# Light_Table_Board.net
KiCad netlist of a schematic drawn in EAGLE
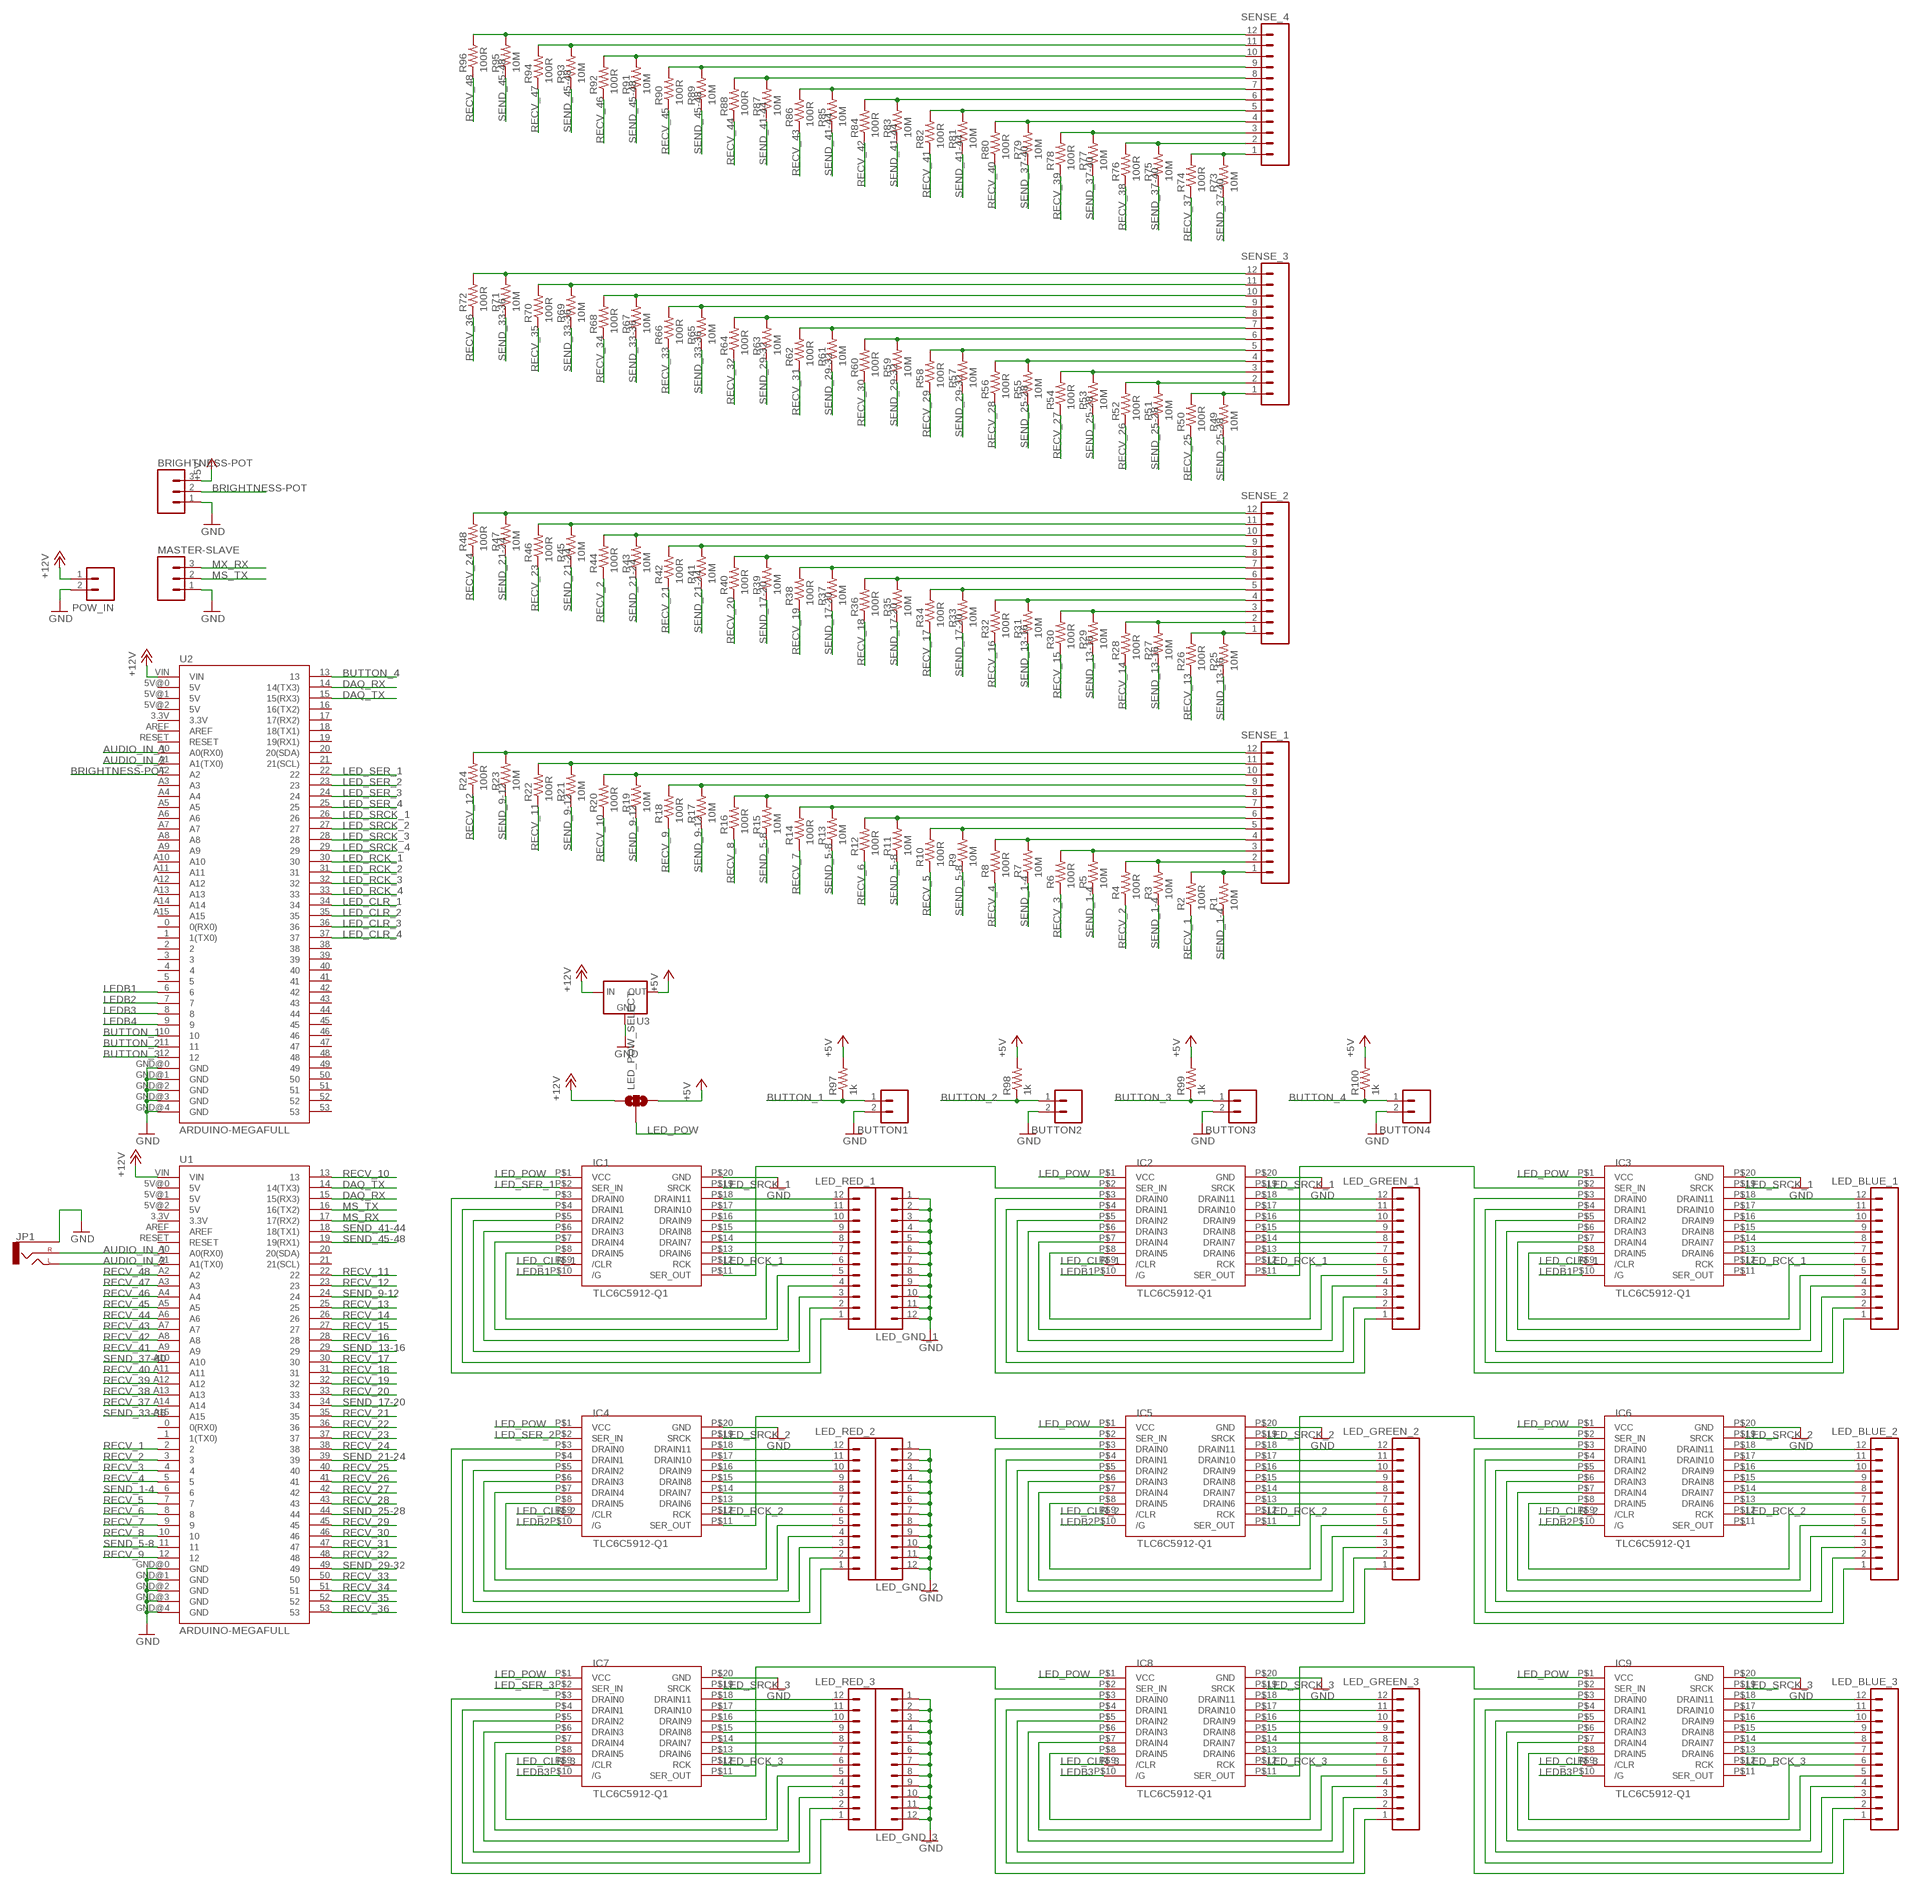
[diagram p0: schematic, sheet 1, part 1 of 2]
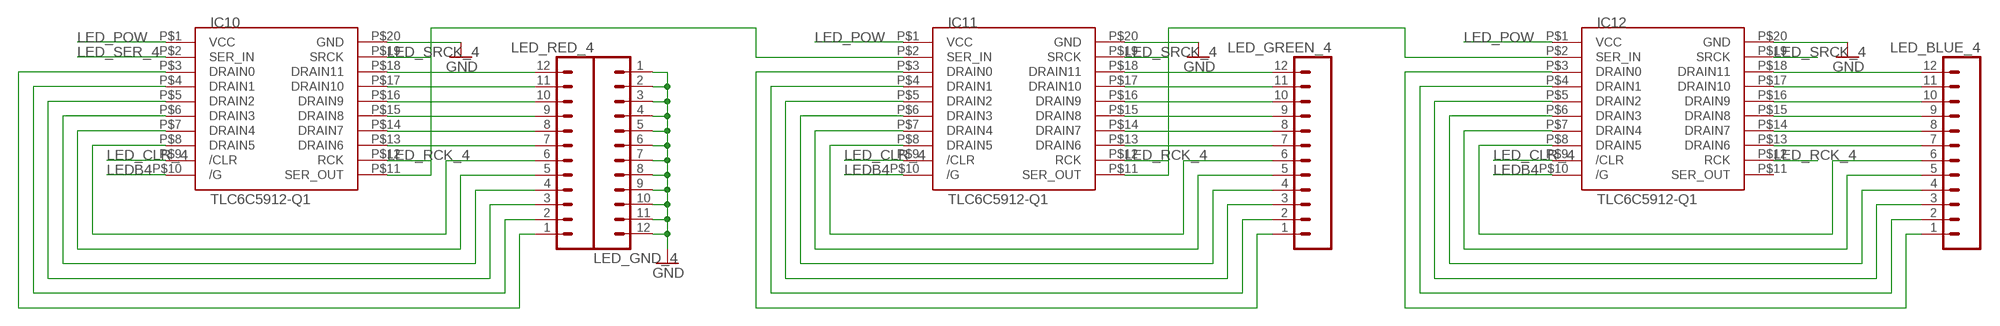
[diagram p1: schematic, sheet 1, part 2 of 2]

(export (version "E")
  (design (tool "Eeschema 10.0.6"))
  (components
    (comp (ref "BRIGHTNESS-POT")
      (value "M03SCREW")
      (footprint "eagle-import:SCREWTERMINAL-3.5MM-3")
      (libsource (lib "eagle-import") (part "M03SCREW"))
    )
    (comp (ref "BUTTON1")
      (value "M023.5MM-NO_SILK")
      (footprint "eagle-import:SCREWTERMINAL-3.5MM-2-NS")
      (libsource (lib "eagle-import") (part "M023.5MM-NO_SILK"))
    )
    (comp (ref "BUTTON2")
      (value "M023.5MM-NO_SILK")
      (footprint "eagle-import:SCREWTERMINAL-3.5MM-2-NS")
      (libsource (lib "eagle-import") (part "M023.5MM-NO_SILK"))
    )
    (comp (ref "BUTTON3")
      (value "M023.5MM-NO_SILK")
      (footprint "eagle-import:SCREWTERMINAL-3.5MM-2-NS")
      (libsource (lib "eagle-import") (part "M023.5MM-NO_SILK"))
    )
    (comp (ref "BUTTON4")
      (value "M023.5MM-NO_SILK")
      (footprint "eagle-import:SCREWTERMINAL-3.5MM-2-NS")
      (libsource (lib "eagle-import") (part "M023.5MM-NO_SILK"))
    )
    (comp (ref "IC1")
      (value "TLC6C5912-Q1")
      (footprint "eagle-import:SOIC-20")
      (libsource (lib "eagle-import") (part "TLC6C5912-Q1"))
    )
    (comp (ref "IC2")
      (value "TLC6C5912-Q1")
      (footprint "eagle-import:SOIC-20")
      (libsource (lib "eagle-import") (part "TLC6C5912-Q1"))
    )
    (comp (ref "IC3")
      (value "TLC6C5912-Q1")
      (footprint "eagle-import:SOIC-20")
      (libsource (lib "eagle-import") (part "TLC6C5912-Q1"))
    )
    (comp (ref "IC4")
      (value "TLC6C5912-Q1")
      (footprint "eagle-import:SOIC-20")
      (libsource (lib "eagle-import") (part "TLC6C5912-Q1"))
    )
    (comp (ref "IC5")
      (value "TLC6C5912-Q1")
      (footprint "eagle-import:SOIC-20")
      (libsource (lib "eagle-import") (part "TLC6C5912-Q1"))
    )
    (comp (ref "IC6")
      (value "TLC6C5912-Q1")
      (footprint "eagle-import:SOIC-20")
      (libsource (lib "eagle-import") (part "TLC6C5912-Q1"))
    )
    (comp (ref "IC7")
      (value "TLC6C5912-Q1")
      (footprint "eagle-import:SOIC-20")
      (libsource (lib "eagle-import") (part "TLC6C5912-Q1"))
    )
    (comp (ref "IC8")
      (value "TLC6C5912-Q1")
      (footprint "eagle-import:SOIC-20")
      (libsource (lib "eagle-import") (part "TLC6C5912-Q1"))
    )
    (comp (ref "IC9")
      (value "TLC6C5912-Q1")
      (footprint "eagle-import:SOIC-20")
      (libsource (lib "eagle-import") (part "TLC6C5912-Q1"))
    )
    (comp (ref "IC10")
      (value "TLC6C5912-Q1")
      (footprint "eagle-import:SOIC-20")
      (libsource (lib "eagle-import") (part "TLC6C5912-Q1"))
    )
    (comp (ref "IC11")
      (value "TLC6C5912-Q1")
      (footprint "eagle-import:SOIC-20")
      (libsource (lib "eagle-import") (part "TLC6C5912-Q1"))
    )
    (comp (ref "IC12")
      (value "TLC6C5912-Q1")
      (footprint "eagle-import:SOIC-20")
      (libsource (lib "eagle-import") (part "TLC6C5912-Q1"))
    )
    (comp (ref "JP1")
      (value "AUDIO-JACK2.5MM")
      (footprint "eagle-import:STEREOJACK2.5MM_STEREOJACK2.5MM")
      (libsource (lib "eagle-import") (part "AUDIO-JACK2.5MM"))
    )
    (comp (ref "LED_BLUE_1")
      (value "M12LONGPADS")
      (footprint "eagle-import:1X12_LONGPADS")
      (libsource (lib "eagle-import") (part "M12LONGPADS"))
    )
    (comp (ref "LED_BLUE_2")
      (value "M12LONGPADS")
      (footprint "eagle-import:1X12_LONGPADS")
      (libsource (lib "eagle-import") (part "M12LONGPADS"))
    )
    (comp (ref "LED_BLUE_3")
      (value "M12LONGPADS")
      (footprint "eagle-import:1X12_LONGPADS")
      (libsource (lib "eagle-import") (part "M12LONGPADS"))
    )
    (comp (ref "LED_BLUE_4")
      (value "M12LONGPADS")
      (footprint "eagle-import:1X12_LONGPADS")
      (libsource (lib "eagle-import") (part "M12LONGPADS"))
    )
    (comp (ref "LED_GND_1")
      (value "M12LONGPADS")
      (footprint "eagle-import:1X12_LONGPADS")
      (libsource (lib "eagle-import") (part "M12LONGPADS"))
    )
    (comp (ref "LED_GND_2")
      (value "M12LONGPADS")
      (footprint "eagle-import:1X12_LONGPADS")
      (libsource (lib "eagle-import") (part "M12LONGPADS"))
    )
    (comp (ref "LED_GND_3")
      (value "M12LONGPADS")
      (footprint "eagle-import:1X12_LONGPADS")
      (libsource (lib "eagle-import") (part "M12LONGPADS"))
    )
    (comp (ref "LED_GND_4")
      (value "M12LONGPADS")
      (footprint "eagle-import:1X12_LONGPADS")
      (libsource (lib "eagle-import") (part "M12LONGPADS"))
    )
    (comp (ref "LED_GREEN_1")
      (value "M12LONGPADS")
      (footprint "eagle-import:1X12_LONGPADS")
      (libsource (lib "eagle-import") (part "M12LONGPADS"))
    )
    (comp (ref "LED_GREEN_2")
      (value "M12LONGPADS")
      (footprint "eagle-import:1X12_LONGPADS")
      (libsource (lib "eagle-import") (part "M12LONGPADS"))
    )
    (comp (ref "LED_GREEN_3")
      (value "M12LONGPADS")
      (footprint "eagle-import:1X12_LONGPADS")
      (libsource (lib "eagle-import") (part "M12LONGPADS"))
    )
    (comp (ref "LED_GREEN_4")
      (value "M12LONGPADS")
      (footprint "eagle-import:1X12_LONGPADS")
      (libsource (lib "eagle-import") (part "M12LONGPADS"))
    )
    (comp (ref "LED_POW_SELECT")
      (value "SOLDERJUMPER_2WAYS")
      (footprint "eagle-import:SJ_3")
      (libsource (lib "eagle-import") (part "SOLDERJUMPER_2WAYS"))
    )
    (comp (ref "LED_RED_1")
      (value "M12LONGPADS")
      (footprint "eagle-import:1X12_LONGPADS")
      (libsource (lib "eagle-import") (part "M12LONGPADS"))
    )
    (comp (ref "LED_RED_2")
      (value "M12LONGPADS")
      (footprint "eagle-import:1X12_LONGPADS")
      (libsource (lib "eagle-import") (part "M12LONGPADS"))
    )
    (comp (ref "LED_RED_3")
      (value "M12LONGPADS")
      (footprint "eagle-import:1X12_LONGPADS")
      (libsource (lib "eagle-import") (part "M12LONGPADS"))
    )
    (comp (ref "LED_RED_4")
      (value "M12LONGPADS")
      (footprint "eagle-import:1X12_LONGPADS")
      (libsource (lib "eagle-import") (part "M12LONGPADS"))
    )
    (comp (ref "MASTER-SLAVE")
      (value "M03SCREW")
      (footprint "eagle-import:SCREWTERMINAL-3.5MM-3")
      (libsource (lib "eagle-import") (part "M03SCREW"))
    )
    (comp (ref "POW_IN")
      (value "M023.5MM-NO_SILK")
      (footprint "eagle-import:SCREWTERMINAL-3.5MM-2-NS")
      (libsource (lib "eagle-import") (part "M023.5MM-NO_SILK"))
    )
    (comp (ref "R1")
      (value "10M")
      (footprint "eagle-import:R1206")
      (libsource (lib "eagle-import") (part "R-US_R1206"))
    )
    (comp (ref "R2")
      (value "100R")
      (footprint "eagle-import:R1206")
      (libsource (lib "eagle-import") (part "R-US_R1206"))
    )
    (comp (ref "R3")
      (value "10M")
      (footprint "eagle-import:R1206")
      (libsource (lib "eagle-import") (part "R-US_R1206"))
    )
    (comp (ref "R4")
      (value "100R")
      (footprint "eagle-import:R1206")
      (libsource (lib "eagle-import") (part "R-US_R1206"))
    )
    (comp (ref "R5")
      (value "10M")
      (footprint "eagle-import:R1206")
      (libsource (lib "eagle-import") (part "R-US_R1206"))
    )
    (comp (ref "R6")
      (value "100R")
      (footprint "eagle-import:R1206")
      (libsource (lib "eagle-import") (part "R-US_R1206"))
    )
    (comp (ref "R7")
      (value "10M")
      (footprint "eagle-import:R1206")
      (libsource (lib "eagle-import") (part "R-US_R1206"))
    )
    (comp (ref "R8")
      (value "100R")
      (footprint "eagle-import:R1206")
      (libsource (lib "eagle-import") (part "R-US_R1206"))
    )
    (comp (ref "R9")
      (value "10M")
      (footprint "eagle-import:R1206")
      (libsource (lib "eagle-import") (part "R-US_R1206"))
    )
    (comp (ref "R10")
      (value "100R")
      (footprint "eagle-import:R1206")
      (libsource (lib "eagle-import") (part "R-US_R1206"))
    )
    (comp (ref "R11")
      (value "10M")
      (footprint "eagle-import:R1206")
      (libsource (lib "eagle-import") (part "R-US_R1206"))
    )
    (comp (ref "R12")
      (value "100R")
      (footprint "eagle-import:R1206")
      (libsource (lib "eagle-import") (part "R-US_R1206"))
    )
    (comp (ref "R13")
      (value "10M")
      (footprint "eagle-import:R1206")
      (libsource (lib "eagle-import") (part "R-US_R1206"))
    )
    (comp (ref "R14")
      (value "100R")
      (footprint "eagle-import:R1206")
      (libsource (lib "eagle-import") (part "R-US_R1206"))
    )
    (comp (ref "R15")
      (value "10M")
      (footprint "eagle-import:R1206")
      (libsource (lib "eagle-import") (part "R-US_R1206"))
    )
    (comp (ref "R16")
      (value "100R")
      (footprint "eagle-import:R1206")
      (libsource (lib "eagle-import") (part "R-US_R1206"))
    )
    (comp (ref "R17")
      (value "10M")
      (footprint "eagle-import:R1206")
      (libsource (lib "eagle-import") (part "R-US_R1206"))
    )
    (comp (ref "R18")
      (value "100R")
      (footprint "eagle-import:R1206")
      (libsource (lib "eagle-import") (part "R-US_R1206"))
    )
    (comp (ref "R19")
      (value "10M")
      (footprint "eagle-import:R1206")
      (libsource (lib "eagle-import") (part "R-US_R1206"))
    )
    (comp (ref "R20")
      (value "100R")
      (footprint "eagle-import:R1206")
      (libsource (lib "eagle-import") (part "R-US_R1206"))
    )
    (comp (ref "R21")
      (value "10M")
      (footprint "eagle-import:R1206")
      (libsource (lib "eagle-import") (part "R-US_R1206"))
    )
    (comp (ref "R22")
      (value "100R")
      (footprint "eagle-import:R1206")
      (libsource (lib "eagle-import") (part "R-US_R1206"))
    )
    (comp (ref "R23")
      (value "10M")
      (footprint "eagle-import:R1206")
      (libsource (lib "eagle-import") (part "R-US_R1206"))
    )
    (comp (ref "R24")
      (value "100R")
      (footprint "eagle-import:R1206")
      (libsource (lib "eagle-import") (part "R-US_R1206"))
    )
    (comp (ref "R25")
      (value "10M")
      (footprint "eagle-import:R1206")
      (libsource (lib "eagle-import") (part "R-US_R1206"))
    )
    (comp (ref "R26")
      (value "100R")
      (footprint "eagle-import:R1206")
      (libsource (lib "eagle-import") (part "R-US_R1206"))
    )
    (comp (ref "R27")
      (value "10M")
      (footprint "eagle-import:R1206")
      (libsource (lib "eagle-import") (part "R-US_R1206"))
    )
    (comp (ref "R28")
      (value "100R")
      (footprint "eagle-import:R1206")
      (libsource (lib "eagle-import") (part "R-US_R1206"))
    )
    (comp (ref "R29")
      (value "10M")
      (footprint "eagle-import:R1206")
      (libsource (lib "eagle-import") (part "R-US_R1206"))
    )
    (comp (ref "R30")
      (value "100R")
      (footprint "eagle-import:R1206")
      (libsource (lib "eagle-import") (part "R-US_R1206"))
    )
    (comp (ref "R31")
      (value "10M")
      (footprint "eagle-import:R1206")
      (libsource (lib "eagle-import") (part "R-US_R1206"))
    )
    (comp (ref "R32")
      (value "100R")
      (footprint "eagle-import:R1206")
      (libsource (lib "eagle-import") (part "R-US_R1206"))
    )
    (comp (ref "R33")
      (value "10M")
      (footprint "eagle-import:R1206")
      (libsource (lib "eagle-import") (part "R-US_R1206"))
    )
    (comp (ref "R34")
      (value "100R")
      (footprint "eagle-import:R1206")
      (libsource (lib "eagle-import") (part "R-US_R1206"))
    )
    (comp (ref "R35")
      (value "10M")
      (footprint "eagle-import:R1206")
      (libsource (lib "eagle-import") (part "R-US_R1206"))
    )
    (comp (ref "R36")
      (value "100R")
      (footprint "eagle-import:R1206")
      (libsource (lib "eagle-import") (part "R-US_R1206"))
    )
    (comp (ref "R37")
      (value "10M")
      (footprint "eagle-import:R1206")
      (libsource (lib "eagle-import") (part "R-US_R1206"))
    )
    (comp (ref "R38")
      (value "100R")
      (footprint "eagle-import:R1206")
      (libsource (lib "eagle-import") (part "R-US_R1206"))
    )
    (comp (ref "R39")
      (value "10M")
      (footprint "eagle-import:R1206")
      (libsource (lib "eagle-import") (part "R-US_R1206"))
    )
    (comp (ref "R40")
      (value "100R")
      (footprint "eagle-import:R1206")
      (libsource (lib "eagle-import") (part "R-US_R1206"))
    )
    (comp (ref "R41")
      (value "10M")
      (footprint "eagle-import:R1206")
      (libsource (lib "eagle-import") (part "R-US_R1206"))
    )
    (comp (ref "R42")
      (value "100R")
      (footprint "eagle-import:R1206")
      (libsource (lib "eagle-import") (part "R-US_R1206"))
    )
    (comp (ref "R43")
      (value "10M")
      (footprint "eagle-import:R1206")
      (libsource (lib "eagle-import") (part "R-US_R1206"))
    )
    (comp (ref "R44")
      (value "100R")
      (footprint "eagle-import:R1206")
      (libsource (lib "eagle-import") (part "R-US_R1206"))
    )
    (comp (ref "R45")
      (value "10M")
      (footprint "eagle-import:R1206")
      (libsource (lib "eagle-import") (part "R-US_R1206"))
    )
    (comp (ref "R46")
      (value "100R")
      (footprint "eagle-import:R1206")
      (libsource (lib "eagle-import") (part "R-US_R1206"))
    )
    (comp (ref "R47")
      (value "10M")
      (footprint "eagle-import:R1206")
      (libsource (lib "eagle-import") (part "R-US_R1206"))
    )
    (comp (ref "R48")
      (value "100R")
      (footprint "eagle-import:R1206")
      (libsource (lib "eagle-import") (part "R-US_R1206"))
    )
    (comp (ref "R49")
      (value "10M")
      (footprint "eagle-import:R1206")
      (libsource (lib "eagle-import") (part "R-US_R1206"))
    )
    (comp (ref "R50")
      (value "100R")
      (footprint "eagle-import:R1206")
      (libsource (lib "eagle-import") (part "R-US_R1206"))
    )
    (comp (ref "R51")
      (value "10M")
      (footprint "eagle-import:R1206")
      (libsource (lib "eagle-import") (part "R-US_R1206"))
    )
    (comp (ref "R52")
      (value "100R")
      (footprint "eagle-import:R1206")
      (libsource (lib "eagle-import") (part "R-US_R1206"))
    )
    (comp (ref "R53")
      (value "10M")
      (footprint "eagle-import:R1206")
      (libsource (lib "eagle-import") (part "R-US_R1206"))
    )
    (comp (ref "R54")
      (value "100R")
      (footprint "eagle-import:R1206")
      (libsource (lib "eagle-import") (part "R-US_R1206"))
    )
    (comp (ref "R55")
      (value "10M")
      (footprint "eagle-import:R1206")
      (libsource (lib "eagle-import") (part "R-US_R1206"))
    )
    (comp (ref "R56")
      (value "100R")
      (footprint "eagle-import:R1206")
      (libsource (lib "eagle-import") (part "R-US_R1206"))
    )
    (comp (ref "R57")
      (value "10M")
      (footprint "eagle-import:R1206")
      (libsource (lib "eagle-import") (part "R-US_R1206"))
    )
    (comp (ref "R58")
      (value "100R")
      (footprint "eagle-import:R1206")
      (libsource (lib "eagle-import") (part "R-US_R1206"))
    )
    (comp (ref "R59")
      (value "10M")
      (footprint "eagle-import:R1206")
      (libsource (lib "eagle-import") (part "R-US_R1206"))
    )
    (comp (ref "R60")
      (value "100R")
      (footprint "eagle-import:R1206")
      (libsource (lib "eagle-import") (part "R-US_R1206"))
    )
    (comp (ref "R61")
      (value "10M")
      (footprint "eagle-import:R1206")
      (libsource (lib "eagle-import") (part "R-US_R1206"))
    )
    (comp (ref "R62")
      (value "100R")
      (footprint "eagle-import:R1206")
      (libsource (lib "eagle-import") (part "R-US_R1206"))
    )
    (comp (ref "R63")
      (value "10M")
      (footprint "eagle-import:R1206")
      (libsource (lib "eagle-import") (part "R-US_R1206"))
    )
    (comp (ref "R64")
      (value "100R")
      (footprint "eagle-import:R1206")
      (libsource (lib "eagle-import") (part "R-US_R1206"))
    )
    (comp (ref "R65")
      (value "10M")
      (footprint "eagle-import:R1206")
      (libsource (lib "eagle-import") (part "R-US_R1206"))
    )
    (comp (ref "R66")
      (value "100R")
      (footprint "eagle-import:R1206")
      (libsource (lib "eagle-import") (part "R-US_R1206"))
    )
    (comp (ref "R67")
      (value "10M")
      (footprint "eagle-import:R1206")
      (libsource (lib "eagle-import") (part "R-US_R1206"))
    )
    (comp (ref "R68")
      (value "100R")
      (footprint "eagle-import:R1206")
      (libsource (lib "eagle-import") (part "R-US_R1206"))
    )
    (comp (ref "R69")
      (value "10M")
      (footprint "eagle-import:R1206")
      (libsource (lib "eagle-import") (part "R-US_R1206"))
    )
    (comp (ref "R70")
      (value "100R")
      (footprint "eagle-import:R1206")
      (libsource (lib "eagle-import") (part "R-US_R1206"))
    )
    (comp (ref "R71")
      (value "10M")
      (footprint "eagle-import:R1206")
      (libsource (lib "eagle-import") (part "R-US_R1206"))
    )
    (comp (ref "R72")
      (value "100R")
      (footprint "eagle-import:R1206")
      (libsource (lib "eagle-import") (part "R-US_R1206"))
    )
    (comp (ref "R73")
      (value "10M")
      (footprint "eagle-import:R1206")
      (libsource (lib "eagle-import") (part "R-US_R1206"))
    )
    (comp (ref "R74")
      (value "100R")
      (footprint "eagle-import:R1206")
      (libsource (lib "eagle-import") (part "R-US_R1206"))
    )
    (comp (ref "R75")
      (value "10M")
      (footprint "eagle-import:R1206")
      (libsource (lib "eagle-import") (part "R-US_R1206"))
    )
    (comp (ref "R76")
      (value "100R")
      (footprint "eagle-import:R1206")
      (libsource (lib "eagle-import") (part "R-US_R1206"))
    )
    (comp (ref "R77")
      (value "10M")
      (footprint "eagle-import:R1206")
      (libsource (lib "eagle-import") (part "R-US_R1206"))
    )
    (comp (ref "R78")
      (value "100R")
      (footprint "eagle-import:R1206")
      (libsource (lib "eagle-import") (part "R-US_R1206"))
    )
    (comp (ref "R79")
      (value "10M")
      (footprint "eagle-import:R1206")
      (libsource (lib "eagle-import") (part "R-US_R1206"))
    )
    (comp (ref "R80")
      (value "100R")
      (footprint "eagle-import:R1206")
      (libsource (lib "eagle-import") (part "R-US_R1206"))
    )
    (comp (ref "R81")
      (value "10M")
      (footprint "eagle-import:R1206")
      (libsource (lib "eagle-import") (part "R-US_R1206"))
    )
    (comp (ref "R82")
      (value "100R")
      (footprint "eagle-import:R1206")
      (libsource (lib "eagle-import") (part "R-US_R1206"))
    )
    (comp (ref "R83")
      (value "10M")
      (footprint "eagle-import:R1206")
      (libsource (lib "eagle-import") (part "R-US_R1206"))
    )
    (comp (ref "R84")
      (value "100R")
      (footprint "eagle-import:R1206")
      (libsource (lib "eagle-import") (part "R-US_R1206"))
    )
    (comp (ref "R85")
      (value "10M")
      (footprint "eagle-import:R1206")
      (libsource (lib "eagle-import") (part "R-US_R1206"))
    )
    (comp (ref "R86")
      (value "100R")
      (footprint "eagle-import:R1206")
      (libsource (lib "eagle-import") (part "R-US_R1206"))
    )
    (comp (ref "R87")
      (value "10M")
      (footprint "eagle-import:R1206")
      (libsource (lib "eagle-import") (part "R-US_R1206"))
    )
    (comp (ref "R88")
      (value "100R")
      (footprint "eagle-import:R1206")
      (libsource (lib "eagle-import") (part "R-US_R1206"))
    )
    (comp (ref "R89")
      (value "10M")
      (footprint "eagle-import:R1206")
      (libsource (lib "eagle-import") (part "R-US_R1206"))
    )
    (comp (ref "R90")
      (value "100R")
      (footprint "eagle-import:R1206")
      (libsource (lib "eagle-import") (part "R-US_R1206"))
    )
    (comp (ref "R91")
      (value "10M")
      (footprint "eagle-import:R1206")
      (libsource (lib "eagle-import") (part "R-US_R1206"))
    )
    (comp (ref "R92")
      (value "100R")
      (footprint "eagle-import:R1206")
      (libsource (lib "eagle-import") (part "R-US_R1206"))
    )
    (comp (ref "R93")
      (value "10M")
      (footprint "eagle-import:R1206")
      (libsource (lib "eagle-import") (part "R-US_R1206"))
    )
    (comp (ref "R94")
      (value "100R")
      (footprint "eagle-import:R1206")
      (libsource (lib "eagle-import") (part "R-US_R1206"))
    )
    (comp (ref "R95")
      (value "10M")
      (footprint "eagle-import:R1206")
      (libsource (lib "eagle-import") (part "R-US_R1206"))
    )
    (comp (ref "R96")
      (value "100R")
      (footprint "eagle-import:R1206")
      (libsource (lib "eagle-import") (part "R-US_R1206"))
    )
    (comp (ref "R97")
      (value "1k")
      (footprint "eagle-import:R1206")
      (libsource (lib "eagle-import") (part "R-US_R1206"))
    )
    (comp (ref "R98")
      (value "1k")
      (footprint "eagle-import:R1206")
      (libsource (lib "eagle-import") (part "R-US_R1206"))
    )
    (comp (ref "R99")
      (value "1k")
      (footprint "eagle-import:R1206")
      (libsource (lib "eagle-import") (part "R-US_R1206"))
    )
    (comp (ref "R100")
      (value "1k")
      (footprint "eagle-import:R1206")
      (libsource (lib "eagle-import") (part "R-US_R1206"))
    )
    (comp (ref "SENSE_1")
      (value "M12LONGPADS")
      (footprint "eagle-import:1X12_LONGPADS")
      (libsource (lib "eagle-import") (part "M12LONGPADS"))
    )
    (comp (ref "SENSE_2")
      (value "M12LONGPADS")
      (footprint "eagle-import:1X12_LONGPADS")
      (libsource (lib "eagle-import") (part "M12LONGPADS"))
    )
    (comp (ref "SENSE_3")
      (value "M12LONGPADS")
      (footprint "eagle-import:1X12_LONGPADS")
      (libsource (lib "eagle-import") (part "M12LONGPADS"))
    )
    (comp (ref "SENSE_4")
      (value "M12LONGPADS")
      (footprint "eagle-import:1X12_LONGPADS")
      (libsource (lib "eagle-import") (part "M12LONGPADS"))
    )
    (comp (ref "U1")
      (value "ARDUINO-MEGAFULL")
      (footprint "eagle-import:ARDUINO_MEGA")
      (libsource (lib "eagle-import") (part "ARDUINO-MEGAFULL"))
    )
    (comp (ref "U2")
      (value "ARDUINO-MEGAFULL")
      (footprint "eagle-import:ARDUINO_MEGA")
      (libsource (lib "eagle-import") (part "ARDUINO-MEGAFULL"))
    )
    (comp (ref "U3")
      (value "V_REG_78XX-TO-220")
      (footprint "eagle-import:TO-220-ALT")
      (libsource (lib "eagle-import") (part "V_REG_78XX-TO-220"))
    )
  )
  (nets
    (net (code "1") (name "+5V") (class "Default")
      (node (ref "BRIGHTNESS-POT") (pin "3") (pinfunction "3_3") (pintype "passive"))
      (node (ref "LED_POW_SELECT") (pin "3") (pinfunction "3_3") (pintype "passive"))
      (node (ref "R100") (pin "2") (pinfunction "2_2") (pintype "passive"))
      (node (ref "R97") (pin "2") (pinfunction "2_2") (pintype "passive"))
      (node (ref "R98") (pin "2") (pinfunction "2_2") (pintype "passive"))
      (node (ref "R99") (pin "2") (pinfunction "2_2") (pintype "passive"))
      (node (ref "U3") (pin "OUT") (pinfunction "OUT_OUT") (pintype "passive"))
    )
    (net (code "2") (name "+12V") (class "Default")
      (node (ref "LED_POW_SELECT") (pin "1") (pinfunction "1_1") (pintype "passive"))
      (node (ref "POW_IN") (pin "1") (pinfunction "1_1") (pintype "passive"))
      (node (ref "U1") (pin "VIN") (pinfunction "VIN_VIN") (pintype "bidirectional"))
      (node (ref "U2") (pin "VIN") (pinfunction "VIN_VIN") (pintype "bidirectional"))
      (node (ref "U3") (pin "IN") (pinfunction "IN_IN") (pintype "input"))
    )
    (net (code "3") (name "/AUDIO_IN_1") (class "Default")
      (node (ref "JP1") (pin "TIP") (pinfunction "RIGHT_TIP") (pintype "bidirectional"))
      (node (ref "U1") (pin "A0") (pinfunction "A0(RX0)_A0") (pintype "bidirectional"))
      (node (ref "U2") (pin "A0") (pinfunction "A0(RX0)_A0") (pintype "bidirectional"))
    )
    (net (code "4") (name "/AUDIO_IN_2") (class "Default")
      (node (ref "JP1") (pin "SHIELD") (pinfunction "LEFT_SHIELD") (pintype "bidirectional"))
      (node (ref "U1") (pin "A1") (pinfunction "A1(TX0)_A1") (pintype "bidirectional"))
      (node (ref "U2") (pin "A1") (pinfunction "A1(TX0)_A1") (pintype "bidirectional"))
    )
    (net (code "5") (name "/BRIGHTNESS-POT") (class "Default")
      (node (ref "BRIGHTNESS-POT") (pin "2") (pinfunction "2_2") (pintype "passive"))
      (node (ref "U2") (pin "A2") (pinfunction "A2_A2") (pintype "bidirectional"))
    )
    (net (code "6") (name "/BUTTON_1") (class "Default")
      (node (ref "BUTTON1") (pin "1") (pinfunction "1_1") (pintype "passive"))
      (node (ref "R97") (pin "1") (pinfunction "1_1") (pintype "passive"))
      (node (ref "U2") (pin "10") (pinfunction "10_10") (pintype "bidirectional"))
    )
    (net (code "7") (name "/BUTTON_2") (class "Default")
      (node (ref "BUTTON2") (pin "1") (pinfunction "1_1") (pintype "passive"))
      (node (ref "R98") (pin "1") (pinfunction "1_1") (pintype "passive"))
      (node (ref "U2") (pin "11") (pinfunction "11_11") (pintype "bidirectional"))
    )
    (net (code "8") (name "/BUTTON_3") (class "Default")
      (node (ref "BUTTON3") (pin "1") (pinfunction "1_1") (pintype "passive"))
      (node (ref "R99") (pin "1") (pinfunction "1_1") (pintype "passive"))
      (node (ref "U2") (pin "12") (pinfunction "12_12") (pintype "bidirectional"))
    )
    (net (code "9") (name "/BUTTON_4") (class "Default")
      (node (ref "BUTTON4") (pin "1") (pinfunction "1_1") (pintype "passive"))
      (node (ref "R100") (pin "1") (pinfunction "1_1") (pintype "passive"))
      (node (ref "U2") (pin "13") (pinfunction "13_13") (pintype "bidirectional"))
    )
    (net (code "10") (name "/DAQ_RX") (class "Default")
      (node (ref "U1") (pin "15") (pinfunction "15(RX3)_15") (pintype "bidirectional"))
      (node (ref "U2") (pin "14") (pinfunction "14(TX3)_14") (pintype "bidirectional"))
    )
    (net (code "11") (name "/DAQ_TX") (class "Default")
      (node (ref "U1") (pin "14") (pinfunction "14(TX3)_14") (pintype "bidirectional"))
      (node (ref "U2") (pin "15") (pinfunction "15(RX3)_15") (pintype "bidirectional"))
    )
    (net (code "12") (name "/LEDB1") (class "Default")
      (node (ref "IC1") (pin "P$10") (pinfunction "/G_P$10") (pintype "bidirectional"))
      (node (ref "IC2") (pin "P$10") (pinfunction "/G_P$10") (pintype "bidirectional"))
      (node (ref "IC3") (pin "P$10") (pinfunction "/G_P$10") (pintype "bidirectional"))
      (node (ref "U2") (pin "6") (pinfunction "6_6") (pintype "bidirectional"))
    )
    (net (code "13") (name "/LEDB2") (class "Default")
      (node (ref "IC4") (pin "P$10") (pinfunction "/G_P$10") (pintype "bidirectional"))
      (node (ref "IC5") (pin "P$10") (pinfunction "/G_P$10") (pintype "bidirectional"))
      (node (ref "IC6") (pin "P$10") (pinfunction "/G_P$10") (pintype "bidirectional"))
      (node (ref "U2") (pin "7") (pinfunction "7_7") (pintype "bidirectional"))
    )
    (net (code "14") (name "/LEDB3") (class "Default")
      (node (ref "IC7") (pin "P$10") (pinfunction "/G_P$10") (pintype "bidirectional"))
      (node (ref "IC8") (pin "P$10") (pinfunction "/G_P$10") (pintype "bidirectional"))
      (node (ref "IC9") (pin "P$10") (pinfunction "/G_P$10") (pintype "bidirectional"))
      (node (ref "U2") (pin "8") (pinfunction "8_8") (pintype "bidirectional"))
    )
    (net (code "15") (name "/LEDB4") (class "Default")
      (node (ref "IC10") (pin "P$10") (pinfunction "/G_P$10") (pintype "bidirectional"))
      (node (ref "IC11") (pin "P$10") (pinfunction "/G_P$10") (pintype "bidirectional"))
      (node (ref "IC12") (pin "P$10") (pinfunction "/G_P$10") (pintype "bidirectional"))
      (node (ref "U2") (pin "9") (pinfunction "9_9") (pintype "bidirectional"))
    )
    (net (code "16") (name "/LED_CLR_1") (class "Default")
      (node (ref "IC1") (pin "P$9") (pinfunction "/CLR_P$9") (pintype "bidirectional"))
      (node (ref "IC2") (pin "P$9") (pinfunction "/CLR_P$9") (pintype "bidirectional"))
      (node (ref "IC3") (pin "P$9") (pinfunction "/CLR_P$9") (pintype "bidirectional"))
      (node (ref "U2") (pin "34") (pinfunction "34_34") (pintype "bidirectional"))
    )
    (net (code "17") (name "/LED_CLR_2") (class "Default")
      (node (ref "IC4") (pin "P$9") (pinfunction "/CLR_P$9") (pintype "bidirectional"))
      (node (ref "IC5") (pin "P$9") (pinfunction "/CLR_P$9") (pintype "bidirectional"))
      (node (ref "IC6") (pin "P$9") (pinfunction "/CLR_P$9") (pintype "bidirectional"))
      (node (ref "U2") (pin "35") (pinfunction "35_35") (pintype "bidirectional"))
    )
    (net (code "18") (name "/LED_CLR_3") (class "Default")
      (node (ref "IC7") (pin "P$9") (pinfunction "/CLR_P$9") (pintype "bidirectional"))
      (node (ref "IC8") (pin "P$9") (pinfunction "/CLR_P$9") (pintype "bidirectional"))
      (node (ref "IC9") (pin "P$9") (pinfunction "/CLR_P$9") (pintype "bidirectional"))
      (node (ref "U2") (pin "36") (pinfunction "36_36") (pintype "bidirectional"))
    )
    (net (code "19") (name "/LED_CLR_4") (class "Default")
      (node (ref "IC10") (pin "P$9") (pinfunction "/CLR_P$9") (pintype "bidirectional"))
      (node (ref "IC11") (pin "P$9") (pinfunction "/CLR_P$9") (pintype "bidirectional"))
      (node (ref "IC12") (pin "P$9") (pinfunction "/CLR_P$9") (pintype "bidirectional"))
      (node (ref "U2") (pin "37") (pinfunction "37_37") (pintype "bidirectional"))
    )
    (net (code "20") (name "/LED_POW") (class "Default")
      (node (ref "IC1") (pin "P$1") (pinfunction "VCC_P$1") (pintype "bidirectional"))
      (node (ref "IC10") (pin "P$1") (pinfunction "VCC_P$1") (pintype "bidirectional"))
      (node (ref "IC11") (pin "P$1") (pinfunction "VCC_P$1") (pintype "bidirectional"))
      (node (ref "IC12") (pin "P$1") (pinfunction "VCC_P$1") (pintype "bidirectional"))
      (node (ref "IC2") (pin "P$1") (pinfunction "VCC_P$1") (pintype "bidirectional"))
      (node (ref "IC3") (pin "P$1") (pinfunction "VCC_P$1") (pintype "bidirectional"))
      (node (ref "IC4") (pin "P$1") (pinfunction "VCC_P$1") (pintype "bidirectional"))
      (node (ref "IC5") (pin "P$1") (pinfunction "VCC_P$1") (pintype "bidirectional"))
      (node (ref "IC6") (pin "P$1") (pinfunction "VCC_P$1") (pintype "bidirectional"))
      (node (ref "IC7") (pin "P$1") (pinfunction "VCC_P$1") (pintype "bidirectional"))
      (node (ref "IC8") (pin "P$1") (pinfunction "VCC_P$1") (pintype "bidirectional"))
      (node (ref "IC9") (pin "P$1") (pinfunction "VCC_P$1") (pintype "bidirectional"))
      (node (ref "LED_POW_SELECT") (pin "2") (pinfunction "2_2") (pintype "passive"))
    )
    (net (code "21") (name "/LED_RCK_1") (class "Default")
      (node (ref "IC1") (pin "P$12") (pinfunction "RCK_P$12") (pintype "bidirectional"))
      (node (ref "IC2") (pin "P$12") (pinfunction "RCK_P$12") (pintype "bidirectional"))
      (node (ref "IC3") (pin "P$12") (pinfunction "RCK_P$12") (pintype "bidirectional"))
      (node (ref "U2") (pin "30") (pinfunction "30_30") (pintype "bidirectional"))
    )
    (net (code "22") (name "/LED_RCK_2") (class "Default")
      (node (ref "IC4") (pin "P$12") (pinfunction "RCK_P$12") (pintype "bidirectional"))
      (node (ref "IC5") (pin "P$12") (pinfunction "RCK_P$12") (pintype "bidirectional"))
      (node (ref "IC6") (pin "P$12") (pinfunction "RCK_P$12") (pintype "bidirectional"))
      (node (ref "U2") (pin "31") (pinfunction "31_31") (pintype "bidirectional"))
    )
    (net (code "23") (name "/LED_RCK_3") (class "Default")
      (node (ref "IC7") (pin "P$12") (pinfunction "RCK_P$12") (pintype "bidirectional"))
      (node (ref "IC8") (pin "P$12") (pinfunction "RCK_P$12") (pintype "bidirectional"))
      (node (ref "IC9") (pin "P$12") (pinfunction "RCK_P$12") (pintype "bidirectional"))
      (node (ref "U2") (pin "32") (pinfunction "32_32") (pintype "bidirectional"))
    )
    (net (code "24") (name "/LED_RCK_4") (class "Default")
      (node (ref "IC10") (pin "P$12") (pinfunction "RCK_P$12") (pintype "bidirectional"))
      (node (ref "IC11") (pin "P$12") (pinfunction "RCK_P$12") (pintype "bidirectional"))
      (node (ref "IC12") (pin "P$12") (pinfunction "RCK_P$12") (pintype "bidirectional"))
      (node (ref "U2") (pin "33") (pinfunction "33_33") (pintype "bidirectional"))
    )
    (net (code "25") (name "/LED_SER_1") (class "Default")
      (node (ref "IC1") (pin "P$2") (pinfunction "SER_IN_P$2") (pintype "bidirectional"))
      (node (ref "U2") (pin "22") (pinfunction "22_22") (pintype "bidirectional"))
    )
    (net (code "26") (name "/LED_SER_2") (class "Default")
      (node (ref "IC4") (pin "P$2") (pinfunction "SER_IN_P$2") (pintype "bidirectional"))
      (node (ref "U2") (pin "23") (pinfunction "23_23") (pintype "bidirectional"))
    )
    (net (code "27") (name "/LED_SER_3") (class "Default")
      (node (ref "IC7") (pin "P$2") (pinfunction "SER_IN_P$2") (pintype "bidirectional"))
      (node (ref "U2") (pin "24") (pinfunction "24_24") (pintype "bidirectional"))
    )
    (net (code "28") (name "/LED_SER_4") (class "Default")
      (node (ref "IC10") (pin "P$2") (pinfunction "SER_IN_P$2") (pintype "bidirectional"))
      (node (ref "U2") (pin "25") (pinfunction "25_25") (pintype "bidirectional"))
    )
    (net (code "29") (name "/LED_SRCK_1") (class "Default")
      (node (ref "IC1") (pin "P$19") (pinfunction "SRCK_P$19") (pintype "bidirectional"))
      (node (ref "IC2") (pin "P$19") (pinfunction "SRCK_P$19") (pintype "bidirectional"))
      (node (ref "IC3") (pin "P$19") (pinfunction "SRCK_P$19") (pintype "bidirectional"))
      (node (ref "U2") (pin "26") (pinfunction "26_26") (pintype "bidirectional"))
    )
    (net (code "30") (name "/LED_SRCK_2") (class "Default")
      (node (ref "IC4") (pin "P$19") (pinfunction "SRCK_P$19") (pintype "bidirectional"))
      (node (ref "IC5") (pin "P$19") (pinfunction "SRCK_P$19") (pintype "bidirectional"))
      (node (ref "IC6") (pin "P$19") (pinfunction "SRCK_P$19") (pintype "bidirectional"))
      (node (ref "U2") (pin "27") (pinfunction "27_27") (pintype "bidirectional"))
    )
    (net (code "31") (name "/LED_SRCK_3") (class "Default")
      (node (ref "IC7") (pin "P$19") (pinfunction "SRCK_P$19") (pintype "bidirectional"))
      (node (ref "IC8") (pin "P$19") (pinfunction "SRCK_P$19") (pintype "bidirectional"))
      (node (ref "IC9") (pin "P$19") (pinfunction "SRCK_P$19") (pintype "bidirectional"))
      (node (ref "U2") (pin "28") (pinfunction "28_28") (pintype "bidirectional"))
    )
    (net (code "32") (name "/LED_SRCK_4") (class "Default")
      (node (ref "IC10") (pin "P$19") (pinfunction "SRCK_P$19") (pintype "bidirectional"))
      (node (ref "IC11") (pin "P$19") (pinfunction "SRCK_P$19") (pintype "bidirectional"))
      (node (ref "IC12") (pin "P$19") (pinfunction "SRCK_P$19") (pintype "bidirectional"))
      (node (ref "U2") (pin "29") (pinfunction "29_29") (pintype "bidirectional"))
    )
    (net (code "33") (name "/MS_RX") (class "Default")
      (node (ref "U1") (pin "17") (pinfunction "17(RX2)_17") (pintype "bidirectional"))
    )
    (net (code "34") (name "/MS_TX") (class "Default")
      (node (ref "MASTER-SLAVE") (pin "2") (pinfunction "2_2") (pintype "passive"))
      (node (ref "U1") (pin "16") (pinfunction "16(TX2)_16") (pintype "bidirectional"))
    )
    (net (code "35") (name "/MX_RX") (class "Default")
      (node (ref "MASTER-SLAVE") (pin "3") (pinfunction "3_3") (pintype "passive"))
    )
    (net (code "36") (name "/RECV_1") (class "Default")
      (node (ref "R2") (pin "1") (pinfunction "1_1") (pintype "passive"))
      (node (ref "U1") (pin "2") (pinfunction "2_2") (pintype "bidirectional"))
    )
    (net (code "37") (name "/RECV_2") (class "Default")
      (node (ref "R4") (pin "1") (pinfunction "1_1") (pintype "passive"))
      (node (ref "R44") (pin "1") (pinfunction "1_1") (pintype "passive"))
      (node (ref "U1") (pin "3") (pinfunction "3_3") (pintype "bidirectional"))
    )
    (net (code "38") (name "/RECV_3") (class "Default")
      (node (ref "R6") (pin "1") (pinfunction "1_1") (pintype "passive"))
      (node (ref "U1") (pin "4") (pinfunction "4_4") (pintype "bidirectional"))
    )
    (net (code "39") (name "/RECV_4") (class "Default")
      (node (ref "R8") (pin "1") (pinfunction "1_1") (pintype "passive"))
      (node (ref "U1") (pin "5") (pinfunction "5_5") (pintype "bidirectional"))
    )
    (net (code "40") (name "/RECV_5") (class "Default")
      (node (ref "R10") (pin "1") (pinfunction "1_1") (pintype "passive"))
      (node (ref "U1") (pin "7") (pinfunction "7_7") (pintype "bidirectional"))
    )
    (net (code "41") (name "/RECV_6") (class "Default")
      (node (ref "R12") (pin "1") (pinfunction "1_1") (pintype "passive"))
      (node (ref "U1") (pin "8") (pinfunction "8_8") (pintype "bidirectional"))
    )
    (net (code "42") (name "/RECV_7") (class "Default")
      (node (ref "R14") (pin "1") (pinfunction "1_1") (pintype "passive"))
      (node (ref "U1") (pin "9") (pinfunction "9_9") (pintype "bidirectional"))
    )
    (net (code "43") (name "/RECV_8") (class "Default")
      (node (ref "R16") (pin "1") (pinfunction "1_1") (pintype "passive"))
      (node (ref "U1") (pin "10") (pinfunction "10_10") (pintype "bidirectional"))
    )
    (net (code "44") (name "/RECV_9") (class "Default")
      (node (ref "R18") (pin "1") (pinfunction "1_1") (pintype "passive"))
      (node (ref "U1") (pin "12") (pinfunction "12_12") (pintype "bidirectional"))
    )
    (net (code "45") (name "/RECV_10") (class "Default")
      (node (ref "R20") (pin "1") (pinfunction "1_1") (pintype "passive"))
      (node (ref "U1") (pin "13") (pinfunction "13_13") (pintype "bidirectional"))
    )
    (net (code "46") (name "/RECV_11") (class "Default")
      (node (ref "R22") (pin "1") (pinfunction "1_1") (pintype "passive"))
      (node (ref "U1") (pin "22") (pinfunction "22_22") (pintype "bidirectional"))
    )
    (net (code "47") (name "/RECV_12") (class "Default")
      (node (ref "R24") (pin "1") (pinfunction "1_1") (pintype "passive"))
      (node (ref "U1") (pin "23") (pinfunction "23_23") (pintype "bidirectional"))
    )
    (net (code "48") (name "/RECV_13") (class "Default")
      (node (ref "R26") (pin "1") (pinfunction "1_1") (pintype "passive"))
      (node (ref "U1") (pin "25") (pinfunction "25_25") (pintype "bidirectional"))
    )
    (net (code "49") (name "/RECV_14") (class "Default")
      (node (ref "R28") (pin "1") (pinfunction "1_1") (pintype "passive"))
      (node (ref "U1") (pin "26") (pinfunction "26_26") (pintype "bidirectional"))
    )
    (net (code "50") (name "/RECV_15") (class "Default")
      (node (ref "R30") (pin "1") (pinfunction "1_1") (pintype "passive"))
      (node (ref "U1") (pin "27") (pinfunction "27_27") (pintype "bidirectional"))
    )
    (net (code "51") (name "/RECV_16") (class "Default")
      (node (ref "R32") (pin "1") (pinfunction "1_1") (pintype "passive"))
      (node (ref "U1") (pin "28") (pinfunction "28_28") (pintype "bidirectional"))
    )
    (net (code "52") (name "/RECV_17") (class "Default")
      (node (ref "R34") (pin "1") (pinfunction "1_1") (pintype "passive"))
      (node (ref "U1") (pin "30") (pinfunction "30_30") (pintype "bidirectional"))
    )
    (net (code "53") (name "/RECV_18") (class "Default")
      (node (ref "R36") (pin "1") (pinfunction "1_1") (pintype "passive"))
      (node (ref "U1") (pin "31") (pinfunction "31_31") (pintype "bidirectional"))
    )
    (net (code "54") (name "/RECV_19") (class "Default")
      (node (ref "R38") (pin "1") (pinfunction "1_1") (pintype "passive"))
      (node (ref "U1") (pin "32") (pinfunction "32_32") (pintype "bidirectional"))
    )
    (net (code "55") (name "/RECV_20") (class "Default")
      (node (ref "R40") (pin "1") (pinfunction "1_1") (pintype "passive"))
      (node (ref "U1") (pin "33") (pinfunction "33_33") (pintype "bidirectional"))
    )
    (net (code "56") (name "/RECV_21") (class "Default")
      (node (ref "R42") (pin "1") (pinfunction "1_1") (pintype "passive"))
      (node (ref "U1") (pin "35") (pinfunction "35_35") (pintype "bidirectional"))
    )
    (net (code "57") (name "/RECV_22") (class "Default")
      (node (ref "U1") (pin "36") (pinfunction "36_36") (pintype "bidirectional"))
    )
    (net (code "58") (name "/RECV_23") (class "Default")
      (node (ref "R46") (pin "1") (pinfunction "1_1") (pintype "passive"))
      (node (ref "U1") (pin "37") (pinfunction "37_37") (pintype "bidirectional"))
    )
    (net (code "59") (name "/RECV_24") (class "Default")
      (node (ref "R48") (pin "1") (pinfunction "1_1") (pintype "passive"))
      (node (ref "U1") (pin "38") (pinfunction "38_38") (pintype "bidirectional"))
    )
    (net (code "60") (name "/RECV_25") (class "Default")
      (node (ref "R50") (pin "1") (pinfunction "1_1") (pintype "passive"))
      (node (ref "U1") (pin "40") (pinfunction "40_40") (pintype "bidirectional"))
    )
    (net (code "61") (name "/RECV_26") (class "Default")
      (node (ref "R52") (pin "1") (pinfunction "1_1") (pintype "passive"))
      (node (ref "U1") (pin "41") (pinfunction "41_41") (pintype "bidirectional"))
    )
    (net (code "62") (name "/RECV_27") (class "Default")
      (node (ref "R54") (pin "1") (pinfunction "1_1") (pintype "passive"))
      (node (ref "U1") (pin "42") (pinfunction "42_42") (pintype "bidirectional"))
    )
    (net (code "63") (name "/RECV_28") (class "Default")
      (node (ref "R56") (pin "1") (pinfunction "1_1") (pintype "passive"))
      (node (ref "U1") (pin "43") (pinfunction "43_43") (pintype "bidirectional"))
    )
    (net (code "64") (name "/RECV_29") (class "Default")
      (node (ref "R58") (pin "1") (pinfunction "1_1") (pintype "passive"))
      (node (ref "U1") (pin "45") (pinfunction "45_45") (pintype "bidirectional"))
    )
    (net (code "65") (name "/RECV_30") (class "Default")
      (node (ref "R60") (pin "1") (pinfunction "1_1") (pintype "passive"))
      (node (ref "U1") (pin "46") (pinfunction "46_46") (pintype "bidirectional"))
    )
    (net (code "66") (name "/RECV_31") (class "Default")
      (node (ref "R62") (pin "1") (pinfunction "1_1") (pintype "passive"))
      (node (ref "U1") (pin "47") (pinfunction "47_47") (pintype "bidirectional"))
    )
    (net (code "67") (name "/RECV_32") (class "Default")
      (node (ref "R64") (pin "1") (pinfunction "1_1") (pintype "passive"))
      (node (ref "U1") (pin "48") (pinfunction "48_48") (pintype "bidirectional"))
    )
    (net (code "68") (name "/RECV_33") (class "Default")
      (node (ref "R66") (pin "1") (pinfunction "1_1") (pintype "passive"))
      (node (ref "U1") (pin "50") (pinfunction "50_50") (pintype "bidirectional"))
    )
    (net (code "69") (name "/RECV_34") (class "Default")
      (node (ref "R68") (pin "1") (pinfunction "1_1") (pintype "passive"))
      (node (ref "U1") (pin "51") (pinfunction "51_51") (pintype "bidirectional"))
    )
    (net (code "70") (name "/RECV_35") (class "Default")
      (node (ref "R70") (pin "1") (pinfunction "1_1") (pintype "passive"))
      (node (ref "U1") (pin "52") (pinfunction "52_52") (pintype "bidirectional"))
    )
    (net (code "71") (name "/RECV_36") (class "Default")
      (node (ref "R72") (pin "1") (pinfunction "1_1") (pintype "passive"))
      (node (ref "U1") (pin "53") (pinfunction "53_53") (pintype "bidirectional"))
    )
    (net (code "72") (name "/RECV_37") (class "Default")
      (node (ref "R74") (pin "1") (pinfunction "1_1") (pintype "passive"))
      (node (ref "U1") (pin "A14") (pinfunction "A14_A14") (pintype "bidirectional"))
    )
    (net (code "73") (name "/RECV_38") (class "Default")
      (node (ref "R76") (pin "1") (pinfunction "1_1") (pintype "passive"))
      (node (ref "U1") (pin "A13") (pinfunction "A13_A13") (pintype "bidirectional"))
    )
    (net (code "74") (name "/RECV_39") (class "Default")
      (node (ref "R78") (pin "1") (pinfunction "1_1") (pintype "passive"))
      (node (ref "U1") (pin "A12") (pinfunction "A12_A12") (pintype "bidirectional"))
    )
    (net (code "75") (name "/RECV_40") (class "Default")
      (node (ref "R80") (pin "1") (pinfunction "1_1") (pintype "passive"))
      (node (ref "U1") (pin "A11") (pinfunction "A11_A11") (pintype "bidirectional"))
    )
    (net (code "76") (name "/RECV_41") (class "Default")
      (node (ref "R82") (pin "1") (pinfunction "1_1") (pintype "passive"))
      (node (ref "U1") (pin "A9") (pinfunction "A9_A9") (pintype "bidirectional"))
    )
    (net (code "77") (name "/RECV_42") (class "Default")
      (node (ref "R84") (pin "1") (pinfunction "1_1") (pintype "passive"))
      (node (ref "U1") (pin "A8") (pinfunction "A8_A8") (pintype "bidirectional"))
    )
    (net (code "78") (name "/RECV_43") (class "Default")
      (node (ref "R86") (pin "1") (pinfunction "1_1") (pintype "passive"))
      (node (ref "U1") (pin "A7") (pinfunction "A7_A7") (pintype "bidirectional"))
    )
    (net (code "79") (name "/RECV_44") (class "Default")
      (node (ref "R88") (pin "1") (pinfunction "1_1") (pintype "passive"))
      (node (ref "U1") (pin "A6") (pinfunction "A6_A6") (pintype "bidirectional"))
    )
    (net (code "80") (name "/RECV_45") (class "Default")
      (node (ref "R90") (pin "1") (pinfunction "1_1") (pintype "passive"))
      (node (ref "U1") (pin "A5") (pinfunction "A5_A5") (pintype "bidirectional"))
    )
    (net (code "81") (name "/RECV_46") (class "Default")
      (node (ref "R92") (pin "1") (pinfunction "1_1") (pintype "passive"))
      (node (ref "U1") (pin "A4") (pinfunction "A4_A4") (pintype "bidirectional"))
    )
    (net (code "82") (name "/RECV_47") (class "Default")
      (node (ref "R94") (pin "1") (pinfunction "1_1") (pintype "passive"))
      (node (ref "U1") (pin "A3") (pinfunction "A3_A3") (pintype "bidirectional"))
    )
    (net (code "83") (name "/RECV_48") (class "Default")
      (node (ref "R96") (pin "1") (pinfunction "1_1") (pintype "passive"))
      (node (ref "U1") (pin "A2") (pinfunction "A2_A2") (pintype "bidirectional"))
    )
    (net (code "84") (name "/SEND_1-4") (class "Default")
      (node (ref "R1") (pin "1") (pinfunction "1_1") (pintype "passive"))
      (node (ref "R3") (pin "1") (pinfunction "1_1") (pintype "passive"))
      (node (ref "R5") (pin "1") (pinfunction "1_1") (pintype "passive"))
      (node (ref "R7") (pin "1") (pinfunction "1_1") (pintype "passive"))
      (node (ref "U1") (pin "6") (pinfunction "6_6") (pintype "bidirectional"))
    )
    (net (code "85") (name "/SEND_5-8") (class "Default")
      (node (ref "R11") (pin "1") (pinfunction "1_1") (pintype "passive"))
      (node (ref "R13") (pin "1") (pinfunction "1_1") (pintype "passive"))
      (node (ref "R15") (pin "1") (pinfunction "1_1") (pintype "passive"))
      (node (ref "R9") (pin "1") (pinfunction "1_1") (pintype "passive"))
      (node (ref "U1") (pin "11") (pinfunction "11_11") (pintype "bidirectional"))
    )
    (net (code "86") (name "/SEND_9-12") (class "Default")
      (node (ref "R17") (pin "1") (pinfunction "1_1") (pintype "passive"))
      (node (ref "R19") (pin "1") (pinfunction "1_1") (pintype "passive"))
      (node (ref "R21") (pin "1") (pinfunction "1_1") (pintype "passive"))
      (node (ref "R23") (pin "1") (pinfunction "1_1") (pintype "passive"))
      (node (ref "U1") (pin "24") (pinfunction "24_24") (pintype "bidirectional"))
    )
    (net (code "87") (name "/SEND_13-16") (class "Default")
      (node (ref "R25") (pin "1") (pinfunction "1_1") (pintype "passive"))
      (node (ref "R27") (pin "1") (pinfunction "1_1") (pintype "passive"))
      (node (ref "R29") (pin "1") (pinfunction "1_1") (pintype "passive"))
      (node (ref "R31") (pin "1") (pinfunction "1_1") (pintype "passive"))
      (node (ref "U1") (pin "29") (pinfunction "29_29") (pintype "bidirectional"))
    )
    (net (code "88") (name "/SEND_17-20") (class "Default")
      (node (ref "R33") (pin "1") (pinfunction "1_1") (pintype "passive"))
      (node (ref "R35") (pin "1") (pinfunction "1_1") (pintype "passive"))
      (node (ref "R37") (pin "1") (pinfunction "1_1") (pintype "passive"))
      (node (ref "R39") (pin "1") (pinfunction "1_1") (pintype "passive"))
      (node (ref "U1") (pin "34") (pinfunction "34_34") (pintype "bidirectional"))
    )
    (net (code "89") (name "/SEND_21-24") (class "Default")
      (node (ref "R41") (pin "1") (pinfunction "1_1") (pintype "passive"))
      (node (ref "R43") (pin "1") (pinfunction "1_1") (pintype "passive"))
      (node (ref "R45") (pin "1") (pinfunction "1_1") (pintype "passive"))
      (node (ref "R47") (pin "1") (pinfunction "1_1") (pintype "passive"))
      (node (ref "U1") (pin "39") (pinfunction "39_39") (pintype "bidirectional"))
    )
    (net (code "90") (name "/SEND_25-28") (class "Default")
      (node (ref "R49") (pin "1") (pinfunction "1_1") (pintype "passive"))
      (node (ref "R51") (pin "1") (pinfunction "1_1") (pintype "passive"))
      (node (ref "R53") (pin "1") (pinfunction "1_1") (pintype "passive"))
      (node (ref "R55") (pin "1") (pinfunction "1_1") (pintype "passive"))
      (node (ref "U1") (pin "44") (pinfunction "44_44") (pintype "bidirectional"))
    )
    (net (code "91") (name "/SEND_29-32") (class "Default")
      (node (ref "R57") (pin "1") (pinfunction "1_1") (pintype "passive"))
      (node (ref "R59") (pin "1") (pinfunction "1_1") (pintype "passive"))
      (node (ref "R61") (pin "1") (pinfunction "1_1") (pintype "passive"))
      (node (ref "R63") (pin "1") (pinfunction "1_1") (pintype "passive"))
      (node (ref "U1") (pin "49") (pinfunction "49_49") (pintype "bidirectional"))
    )
    (net (code "92") (name "/SEND_33-36") (class "Default")
      (node (ref "R65") (pin "1") (pinfunction "1_1") (pintype "passive"))
      (node (ref "R67") (pin "1") (pinfunction "1_1") (pintype "passive"))
      (node (ref "R69") (pin "1") (pinfunction "1_1") (pintype "passive"))
      (node (ref "R71") (pin "1") (pinfunction "1_1") (pintype "passive"))
      (node (ref "U1") (pin "A15") (pinfunction "A15_A15") (pintype "bidirectional"))
    )
    (net (code "93") (name "/SEND_37-40") (class "Default")
      (node (ref "R73") (pin "1") (pinfunction "1_1") (pintype "passive"))
      (node (ref "R75") (pin "1") (pinfunction "1_1") (pintype "passive"))
      (node (ref "R77") (pin "1") (pinfunction "1_1") (pintype "passive"))
      (node (ref "R79") (pin "1") (pinfunction "1_1") (pintype "passive"))
      (node (ref "U1") (pin "A10") (pinfunction "A10_A10") (pintype "bidirectional"))
    )
    (net (code "94") (name "/SEND_41-44") (class "Default")
      (node (ref "R81") (pin "1") (pinfunction "1_1") (pintype "passive"))
      (node (ref "R83") (pin "1") (pinfunction "1_1") (pintype "passive"))
      (node (ref "R85") (pin "1") (pinfunction "1_1") (pintype "passive"))
      (node (ref "R87") (pin "1") (pinfunction "1_1") (pintype "passive"))
      (node (ref "U1") (pin "18") (pinfunction "18(TX1)_18") (pintype "bidirectional"))
    )
    (net (code "95") (name "/SEND_45-48") (class "Default")
      (node (ref "R89") (pin "1") (pinfunction "1_1") (pintype "passive"))
      (node (ref "R91") (pin "1") (pinfunction "1_1") (pintype "passive"))
      (node (ref "R93") (pin "1") (pinfunction "1_1") (pintype "passive"))
      (node (ref "R95") (pin "1") (pinfunction "1_1") (pintype "passive"))
      (node (ref "U1") (pin "19") (pinfunction "19(RX1)_19") (pintype "bidirectional"))
    )
    (net (code "96") (name "GND") (class "Default")
      (node (ref "BRIGHTNESS-POT") (pin "1") (pinfunction "1_1") (pintype "passive"))
      (node (ref "BUTTON1") (pin "2") (pinfunction "2_2") (pintype "passive"))
      (node (ref "BUTTON2") (pin "2") (pinfunction "2_2") (pintype "passive"))
      (node (ref "BUTTON3") (pin "2") (pinfunction "2_2") (pintype "passive"))
      (node (ref "BUTTON4") (pin "2") (pinfunction "2_2") (pintype "passive"))
      (node (ref "IC1") (pin "P$20") (pinfunction "GND_P$20") (pintype "bidirectional"))
      (node (ref "IC10") (pin "P$20") (pinfunction "GND_P$20") (pintype "bidirectional"))
      (node (ref "IC11") (pin "P$20") (pinfunction "GND_P$20") (pintype "bidirectional"))
      (node (ref "IC12") (pin "P$20") (pinfunction "GND_P$20") (pintype "bidirectional"))
      (node (ref "IC2") (pin "P$20") (pinfunction "GND_P$20") (pintype "bidirectional"))
      (node (ref "IC3") (pin "P$20") (pinfunction "GND_P$20") (pintype "bidirectional"))
      (node (ref "IC4") (pin "P$20") (pinfunction "GND_P$20") (pintype "bidirectional"))
      (node (ref "IC5") (pin "P$20") (pinfunction "GND_P$20") (pintype "bidirectional"))
      (node (ref "IC6") (pin "P$20") (pinfunction "GND_P$20") (pintype "bidirectional"))
      (node (ref "IC7") (pin "P$20") (pinfunction "GND_P$20") (pintype "bidirectional"))
      (node (ref "IC8") (pin "P$20") (pinfunction "GND_P$20") (pintype "bidirectional"))
      (node (ref "IC9") (pin "P$20") (pinfunction "GND_P$20") (pintype "bidirectional"))
      (node (ref "JP1") (pin "RING1") (pinfunction "SLEEVE_RING1") (pintype "bidirectional"))
      (node (ref "LED_GND_1") (pin "1") (pinfunction "1_1") (pintype "passive"))
      (node (ref "LED_GND_1") (pin "10") (pinfunction "10_10") (pintype "passive"))
      (node (ref "LED_GND_1") (pin "11") (pinfunction "11_11") (pintype "passive"))
      (node (ref "LED_GND_1") (pin "12") (pinfunction "12_12") (pintype "passive"))
      (node (ref "LED_GND_1") (pin "2") (pinfunction "2_2") (pintype "passive"))
      (node (ref "LED_GND_1") (pin "3") (pinfunction "3_3") (pintype "passive"))
      (node (ref "LED_GND_1") (pin "4") (pinfunction "4_4") (pintype "passive"))
      (node (ref "LED_GND_1") (pin "5") (pinfunction "5_5") (pintype "passive"))
      (node (ref "LED_GND_1") (pin "6") (pinfunction "6_6") (pintype "passive"))
      (node (ref "LED_GND_1") (pin "7") (pinfunction "7_7") (pintype "passive"))
      (node (ref "LED_GND_1") (pin "8") (pinfunction "8_8") (pintype "passive"))
      (node (ref "LED_GND_1") (pin "9") (pinfunction "9_9") (pintype "passive"))
      (node (ref "LED_GND_2") (pin "1") (pinfunction "1_1") (pintype "passive"))
      (node (ref "LED_GND_2") (pin "10") (pinfunction "10_10") (pintype "passive"))
      (node (ref "LED_GND_2") (pin "11") (pinfunction "11_11") (pintype "passive"))
      (node (ref "LED_GND_2") (pin "12") (pinfunction "12_12") (pintype "passive"))
      (node (ref "LED_GND_2") (pin "2") (pinfunction "2_2") (pintype "passive"))
      (node (ref "LED_GND_2") (pin "3") (pinfunction "3_3") (pintype "passive"))
      (node (ref "LED_GND_2") (pin "4") (pinfunction "4_4") (pintype "passive"))
      (node (ref "LED_GND_2") (pin "5") (pinfunction "5_5") (pintype "passive"))
      (node (ref "LED_GND_2") (pin "6") (pinfunction "6_6") (pintype "passive"))
      (node (ref "LED_GND_2") (pin "7") (pinfunction "7_7") (pintype "passive"))
      (node (ref "LED_GND_2") (pin "8") (pinfunction "8_8") (pintype "passive"))
      (node (ref "LED_GND_2") (pin "9") (pinfunction "9_9") (pintype "passive"))
      (node (ref "LED_GND_3") (pin "1") (pinfunction "1_1") (pintype "passive"))
      (node (ref "LED_GND_3") (pin "10") (pinfunction "10_10") (pintype "passive"))
      (node (ref "LED_GND_3") (pin "11") (pinfunction "11_11") (pintype "passive"))
      (node (ref "LED_GND_3") (pin "12") (pinfunction "12_12") (pintype "passive"))
      (node (ref "LED_GND_3") (pin "2") (pinfunction "2_2") (pintype "passive"))
      (node (ref "LED_GND_3") (pin "3") (pinfunction "3_3") (pintype "passive"))
      (node (ref "LED_GND_3") (pin "4") (pinfunction "4_4") (pintype "passive"))
      (node (ref "LED_GND_3") (pin "5") (pinfunction "5_5") (pintype "passive"))
      (node (ref "LED_GND_3") (pin "6") (pinfunction "6_6") (pintype "passive"))
      (node (ref "LED_GND_3") (pin "7") (pinfunction "7_7") (pintype "passive"))
      (node (ref "LED_GND_3") (pin "8") (pinfunction "8_8") (pintype "passive"))
      (node (ref "LED_GND_3") (pin "9") (pinfunction "9_9") (pintype "passive"))
      (node (ref "LED_GND_4") (pin "1") (pinfunction "1_1") (pintype "passive"))
      (node (ref "LED_GND_4") (pin "10") (pinfunction "10_10") (pintype "passive"))
      (node (ref "LED_GND_4") (pin "11") (pinfunction "11_11") (pintype "passive"))
      (node (ref "LED_GND_4") (pin "12") (pinfunction "12_12") (pintype "passive"))
      (node (ref "LED_GND_4") (pin "2") (pinfunction "2_2") (pintype "passive"))
      (node (ref "LED_GND_4") (pin "3") (pinfunction "3_3") (pintype "passive"))
      (node (ref "LED_GND_4") (pin "4") (pinfunction "4_4") (pintype "passive"))
      (node (ref "LED_GND_4") (pin "5") (pinfunction "5_5") (pintype "passive"))
      (node (ref "LED_GND_4") (pin "6") (pinfunction "6_6") (pintype "passive"))
      (node (ref "LED_GND_4") (pin "7") (pinfunction "7_7") (pintype "passive"))
      (node (ref "LED_GND_4") (pin "8") (pinfunction "8_8") (pintype "passive"))
      (node (ref "LED_GND_4") (pin "9") (pinfunction "9_9") (pintype "passive"))
      (node (ref "MASTER-SLAVE") (pin "1") (pinfunction "1_1") (pintype "passive"))
      (node (ref "POW_IN") (pin "2") (pinfunction "2_2") (pintype "passive"))
      (node (ref "U1") (pin "GND@0") (pinfunction "GND_GND@0") (pintype "bidirectional"))
      (node (ref "U1") (pin "GND@1") (pinfunction "GND_GND@1") (pintype "bidirectional"))
      (node (ref "U1") (pin "GND@2") (pinfunction "GND_GND@2") (pintype "bidirectional"))
      (node (ref "U1") (pin "GND@3") (pinfunction "GND_GND@3") (pintype "bidirectional"))
      (node (ref "U1") (pin "GND@4") (pinfunction "GND_GND@4") (pintype "bidirectional"))
      (node (ref "U2") (pin "GND@0") (pinfunction "GND_GND@0") (pintype "bidirectional"))
      (node (ref "U2") (pin "GND@1") (pinfunction "GND_GND@1") (pintype "bidirectional"))
      (node (ref "U2") (pin "GND@2") (pinfunction "GND_GND@2") (pintype "bidirectional"))
      (node (ref "U2") (pin "GND@3") (pinfunction "GND_GND@3") (pintype "bidirectional"))
      (node (ref "U2") (pin "GND@4") (pinfunction "GND_GND@4") (pintype "bidirectional"))
      (node (ref "U3") (pin "GND") (pinfunction "GND_GND") (pintype "input"))
    )
    (net (code "97") (name "Net-(IC1-DRAIN0)") (class "Default")
      (node (ref "IC1") (pin "P$3") (pinfunction "DRAIN0_P$3") (pintype "bidirectional"))
      (node (ref "LED_RED_1") (pin "1") (pinfunction "1_1") (pintype "passive"))
    )
    (net (code "98") (name "Net-(IC1-DRAIN1)") (class "Default")
      (node (ref "IC1") (pin "P$4") (pinfunction "DRAIN1_P$4") (pintype "bidirectional"))
      (node (ref "LED_RED_1") (pin "2") (pinfunction "2_2") (pintype "passive"))
    )
    (net (code "99") (name "Net-(IC1-DRAIN2)") (class "Default")
      (node (ref "IC1") (pin "P$5") (pinfunction "DRAIN2_P$5") (pintype "bidirectional"))
      (node (ref "LED_RED_1") (pin "3") (pinfunction "3_3") (pintype "passive"))
    )
    (net (code "100") (name "Net-(IC1-DRAIN3)") (class "Default")
      (node (ref "IC1") (pin "P$6") (pinfunction "DRAIN3_P$6") (pintype "bidirectional"))
      (node (ref "LED_RED_1") (pin "4") (pinfunction "4_4") (pintype "passive"))
    )
    (net (code "101") (name "Net-(IC1-DRAIN4)") (class "Default")
      (node (ref "IC1") (pin "P$7") (pinfunction "DRAIN4_P$7") (pintype "bidirectional"))
      (node (ref "LED_RED_1") (pin "5") (pinfunction "5_5") (pintype "passive"))
    )
    (net (code "102") (name "Net-(IC1-DRAIN5)") (class "Default")
      (node (ref "IC1") (pin "P$8") (pinfunction "DRAIN5_P$8") (pintype "bidirectional"))
      (node (ref "LED_RED_1") (pin "6") (pinfunction "6_6") (pintype "passive"))
    )
    (net (code "103") (name "Net-(IC1-DRAIN6)") (class "Default")
      (node (ref "IC1") (pin "P$13") (pinfunction "DRAIN6_P$13") (pintype "bidirectional"))
      (node (ref "LED_RED_1") (pin "7") (pinfunction "7_7") (pintype "passive"))
    )
    (net (code "104") (name "Net-(IC1-DRAIN7)") (class "Default")
      (node (ref "IC1") (pin "P$14") (pinfunction "DRAIN7_P$14") (pintype "bidirectional"))
      (node (ref "LED_RED_1") (pin "8") (pinfunction "8_8") (pintype "passive"))
    )
    (net (code "105") (name "Net-(IC1-DRAIN8)") (class "Default")
      (node (ref "IC1") (pin "P$15") (pinfunction "DRAIN8_P$15") (pintype "bidirectional"))
      (node (ref "LED_RED_1") (pin "9") (pinfunction "9_9") (pintype "passive"))
    )
    (net (code "106") (name "Net-(IC1-DRAIN9)") (class "Default")
      (node (ref "IC1") (pin "P$16") (pinfunction "DRAIN9_P$16") (pintype "bidirectional"))
      (node (ref "LED_RED_1") (pin "10") (pinfunction "10_10") (pintype "passive"))
    )
    (net (code "107") (name "Net-(IC1-DRAIN10)") (class "Default")
      (node (ref "IC1") (pin "P$17") (pinfunction "DRAIN10_P$17") (pintype "bidirectional"))
      (node (ref "LED_RED_1") (pin "11") (pinfunction "11_11") (pintype "passive"))
    )
    (net (code "108") (name "Net-(IC1-DRAIN11)") (class "Default")
      (node (ref "IC1") (pin "P$18") (pinfunction "DRAIN11_P$18") (pintype "bidirectional"))
      (node (ref "LED_RED_1") (pin "12") (pinfunction "12_12") (pintype "passive"))
    )
    (net (code "109") (name "Net-(IC1-SER_OUT)") (class "Default")
      (node (ref "IC1") (pin "P$11") (pinfunction "SER_OUT_P$11") (pintype "bidirectional"))
      (node (ref "IC2") (pin "P$2") (pinfunction "SER_IN_P$2") (pintype "bidirectional"))
    )
    (net (code "110") (name "Net-(IC2-DRAIN0)") (class "Default")
      (node (ref "IC2") (pin "P$3") (pinfunction "DRAIN0_P$3") (pintype "bidirectional"))
      (node (ref "LED_GREEN_1") (pin "1") (pinfunction "1_1") (pintype "passive"))
    )
    (net (code "111") (name "Net-(IC2-DRAIN1)") (class "Default")
      (node (ref "IC2") (pin "P$4") (pinfunction "DRAIN1_P$4") (pintype "bidirectional"))
      (node (ref "LED_GREEN_1") (pin "2") (pinfunction "2_2") (pintype "passive"))
    )
    (net (code "112") (name "Net-(IC2-DRAIN2)") (class "Default")
      (node (ref "IC2") (pin "P$5") (pinfunction "DRAIN2_P$5") (pintype "bidirectional"))
      (node (ref "LED_GREEN_1") (pin "3") (pinfunction "3_3") (pintype "passive"))
    )
    (net (code "113") (name "Net-(IC2-DRAIN3)") (class "Default")
      (node (ref "IC2") (pin "P$6") (pinfunction "DRAIN3_P$6") (pintype "bidirectional"))
      (node (ref "LED_GREEN_1") (pin "4") (pinfunction "4_4") (pintype "passive"))
    )
    (net (code "114") (name "Net-(IC2-DRAIN4)") (class "Default")
      (node (ref "IC2") (pin "P$7") (pinfunction "DRAIN4_P$7") (pintype "bidirectional"))
      (node (ref "LED_GREEN_1") (pin "5") (pinfunction "5_5") (pintype "passive"))
    )
    (net (code "115") (name "Net-(IC2-DRAIN5)") (class "Default")
      (node (ref "IC2") (pin "P$8") (pinfunction "DRAIN5_P$8") (pintype "bidirectional"))
      (node (ref "LED_GREEN_1") (pin "6") (pinfunction "6_6") (pintype "passive"))
    )
    (net (code "116") (name "Net-(IC2-DRAIN6)") (class "Default")
      (node (ref "IC2") (pin "P$13") (pinfunction "DRAIN6_P$13") (pintype "bidirectional"))
      (node (ref "LED_GREEN_1") (pin "7") (pinfunction "7_7") (pintype "passive"))
    )
    (net (code "117") (name "Net-(IC2-DRAIN7)") (class "Default")
      (node (ref "IC2") (pin "P$14") (pinfunction "DRAIN7_P$14") (pintype "bidirectional"))
      (node (ref "LED_GREEN_1") (pin "8") (pinfunction "8_8") (pintype "passive"))
    )
    (net (code "118") (name "Net-(IC2-DRAIN8)") (class "Default")
      (node (ref "IC2") (pin "P$15") (pinfunction "DRAIN8_P$15") (pintype "bidirectional"))
      (node (ref "LED_GREEN_1") (pin "9") (pinfunction "9_9") (pintype "passive"))
    )
    (net (code "119") (name "Net-(IC2-DRAIN9)") (class "Default")
      (node (ref "IC2") (pin "P$16") (pinfunction "DRAIN9_P$16") (pintype "bidirectional"))
      (node (ref "LED_GREEN_1") (pin "10") (pinfunction "10_10") (pintype "passive"))
    )
    (net (code "120") (name "Net-(IC2-DRAIN10)") (class "Default")
      (node (ref "IC2") (pin "P$17") (pinfunction "DRAIN10_P$17") (pintype "bidirectional"))
      (node (ref "LED_GREEN_1") (pin "11") (pinfunction "11_11") (pintype "passive"))
    )
    (net (code "121") (name "Net-(IC2-DRAIN11)") (class "Default")
      (node (ref "IC2") (pin "P$18") (pinfunction "DRAIN11_P$18") (pintype "bidirectional"))
      (node (ref "LED_GREEN_1") (pin "12") (pinfunction "12_12") (pintype "passive"))
    )
    (net (code "122") (name "Net-(IC2-SER_OUT)") (class "Default")
      (node (ref "IC2") (pin "P$11") (pinfunction "SER_OUT_P$11") (pintype "bidirectional"))
      (node (ref "IC3") (pin "P$2") (pinfunction "SER_IN_P$2") (pintype "bidirectional"))
    )
    (net (code "123") (name "Net-(IC3-DRAIN0)") (class "Default")
      (node (ref "IC3") (pin "P$3") (pinfunction "DRAIN0_P$3") (pintype "bidirectional"))
      (node (ref "LED_BLUE_1") (pin "1") (pinfunction "1_1") (pintype "passive"))
    )
    (net (code "124") (name "Net-(IC3-DRAIN1)") (class "Default")
      (node (ref "IC3") (pin "P$4") (pinfunction "DRAIN1_P$4") (pintype "bidirectional"))
      (node (ref "LED_BLUE_1") (pin "2") (pinfunction "2_2") (pintype "passive"))
    )
    (net (code "125") (name "Net-(IC3-DRAIN2)") (class "Default")
      (node (ref "IC3") (pin "P$5") (pinfunction "DRAIN2_P$5") (pintype "bidirectional"))
      (node (ref "LED_BLUE_1") (pin "3") (pinfunction "3_3") (pintype "passive"))
    )
    (net (code "126") (name "Net-(IC3-DRAIN3)") (class "Default")
      (node (ref "IC3") (pin "P$6") (pinfunction "DRAIN3_P$6") (pintype "bidirectional"))
      (node (ref "LED_BLUE_1") (pin "4") (pinfunction "4_4") (pintype "passive"))
    )
    (net (code "127") (name "Net-(IC3-DRAIN4)") (class "Default")
      (node (ref "IC3") (pin "P$7") (pinfunction "DRAIN4_P$7") (pintype "bidirectional"))
      (node (ref "LED_BLUE_1") (pin "5") (pinfunction "5_5") (pintype "passive"))
    )
    (net (code "128") (name "Net-(IC3-DRAIN5)") (class "Default")
      (node (ref "IC3") (pin "P$8") (pinfunction "DRAIN5_P$8") (pintype "bidirectional"))
      (node (ref "LED_BLUE_1") (pin "6") (pinfunction "6_6") (pintype "passive"))
    )
    (net (code "129") (name "Net-(IC3-DRAIN6)") (class "Default")
      (node (ref "IC3") (pin "P$13") (pinfunction "DRAIN6_P$13") (pintype "bidirectional"))
      (node (ref "LED_BLUE_1") (pin "7") (pinfunction "7_7") (pintype "passive"))
    )
    (net (code "130") (name "Net-(IC3-DRAIN7)") (class "Default")
      (node (ref "IC3") (pin "P$14") (pinfunction "DRAIN7_P$14") (pintype "bidirectional"))
      (node (ref "LED_BLUE_1") (pin "8") (pinfunction "8_8") (pintype "passive"))
    )
    (net (code "131") (name "Net-(IC3-DRAIN8)") (class "Default")
      (node (ref "IC3") (pin "P$15") (pinfunction "DRAIN8_P$15") (pintype "bidirectional"))
      (node (ref "LED_BLUE_1") (pin "9") (pinfunction "9_9") (pintype "passive"))
    )
    (net (code "132") (name "Net-(IC3-DRAIN9)") (class "Default")
      (node (ref "IC3") (pin "P$16") (pinfunction "DRAIN9_P$16") (pintype "bidirectional"))
      (node (ref "LED_BLUE_1") (pin "10") (pinfunction "10_10") (pintype "passive"))
    )
    (net (code "133") (name "Net-(IC3-DRAIN10)") (class "Default")
      (node (ref "IC3") (pin "P$17") (pinfunction "DRAIN10_P$17") (pintype "bidirectional"))
      (node (ref "LED_BLUE_1") (pin "11") (pinfunction "11_11") (pintype "passive"))
    )
    (net (code "134") (name "Net-(IC3-DRAIN11)") (class "Default")
      (node (ref "IC3") (pin "P$18") (pinfunction "DRAIN11_P$18") (pintype "bidirectional"))
      (node (ref "LED_BLUE_1") (pin "12") (pinfunction "12_12") (pintype "passive"))
    )
    (net (code "135") (name "Net-(IC4-DRAIN0)") (class "Default")
      (node (ref "IC4") (pin "P$3") (pinfunction "DRAIN0_P$3") (pintype "bidirectional"))
      (node (ref "LED_RED_2") (pin "1") (pinfunction "1_1") (pintype "passive"))
    )
    (net (code "136") (name "Net-(IC4-DRAIN1)") (class "Default")
      (node (ref "IC4") (pin "P$4") (pinfunction "DRAIN1_P$4") (pintype "bidirectional"))
      (node (ref "LED_RED_2") (pin "2") (pinfunction "2_2") (pintype "passive"))
    )
    (net (code "137") (name "Net-(IC4-DRAIN2)") (class "Default")
      (node (ref "IC4") (pin "P$5") (pinfunction "DRAIN2_P$5") (pintype "bidirectional"))
      (node (ref "LED_RED_2") (pin "3") (pinfunction "3_3") (pintype "passive"))
    )
    (net (code "138") (name "Net-(IC4-DRAIN3)") (class "Default")
      (node (ref "IC4") (pin "P$6") (pinfunction "DRAIN3_P$6") (pintype "bidirectional"))
      (node (ref "LED_RED_2") (pin "4") (pinfunction "4_4") (pintype "passive"))
    )
    (net (code "139") (name "Net-(IC4-DRAIN4)") (class "Default")
      (node (ref "IC4") (pin "P$7") (pinfunction "DRAIN4_P$7") (pintype "bidirectional"))
      (node (ref "LED_RED_2") (pin "5") (pinfunction "5_5") (pintype "passive"))
    )
    (net (code "140") (name "Net-(IC4-DRAIN5)") (class "Default")
      (node (ref "IC4") (pin "P$8") (pinfunction "DRAIN5_P$8") (pintype "bidirectional"))
      (node (ref "LED_RED_2") (pin "6") (pinfunction "6_6") (pintype "passive"))
    )
    (net (code "141") (name "Net-(IC4-DRAIN6)") (class "Default")
      (node (ref "IC4") (pin "P$13") (pinfunction "DRAIN6_P$13") (pintype "bidirectional"))
      (node (ref "LED_RED_2") (pin "7") (pinfunction "7_7") (pintype "passive"))
    )
    (net (code "142") (name "Net-(IC4-DRAIN7)") (class "Default")
      (node (ref "IC4") (pin "P$14") (pinfunction "DRAIN7_P$14") (pintype "bidirectional"))
      (node (ref "LED_RED_2") (pin "8") (pinfunction "8_8") (pintype "passive"))
    )
    (net (code "143") (name "Net-(IC4-DRAIN8)") (class "Default")
      (node (ref "IC4") (pin "P$15") (pinfunction "DRAIN8_P$15") (pintype "bidirectional"))
      (node (ref "LED_RED_2") (pin "9") (pinfunction "9_9") (pintype "passive"))
    )
    (net (code "144") (name "Net-(IC4-DRAIN9)") (class "Default")
      (node (ref "IC4") (pin "P$16") (pinfunction "DRAIN9_P$16") (pintype "bidirectional"))
      (node (ref "LED_RED_2") (pin "10") (pinfunction "10_10") (pintype "passive"))
    )
    (net (code "145") (name "Net-(IC4-DRAIN10)") (class "Default")
      (node (ref "IC4") (pin "P$17") (pinfunction "DRAIN10_P$17") (pintype "bidirectional"))
      (node (ref "LED_RED_2") (pin "11") (pinfunction "11_11") (pintype "passive"))
    )
    (net (code "146") (name "Net-(IC4-DRAIN11)") (class "Default")
      (node (ref "IC4") (pin "P$18") (pinfunction "DRAIN11_P$18") (pintype "bidirectional"))
      (node (ref "LED_RED_2") (pin "12") (pinfunction "12_12") (pintype "passive"))
    )
    (net (code "147") (name "Net-(IC4-SER_OUT)") (class "Default")
      (node (ref "IC4") (pin "P$11") (pinfunction "SER_OUT_P$11") (pintype "bidirectional"))
      (node (ref "IC5") (pin "P$2") (pinfunction "SER_IN_P$2") (pintype "bidirectional"))
    )
    (net (code "148") (name "Net-(IC5-DRAIN0)") (class "Default")
      (node (ref "IC5") (pin "P$3") (pinfunction "DRAIN0_P$3") (pintype "bidirectional"))
      (node (ref "LED_GREEN_2") (pin "1") (pinfunction "1_1") (pintype "passive"))
    )
    (net (code "149") (name "Net-(IC5-DRAIN1)") (class "Default")
      (node (ref "IC5") (pin "P$4") (pinfunction "DRAIN1_P$4") (pintype "bidirectional"))
      (node (ref "LED_GREEN_2") (pin "2") (pinfunction "2_2") (pintype "passive"))
    )
    (net (code "150") (name "Net-(IC5-DRAIN2)") (class "Default")
      (node (ref "IC5") (pin "P$5") (pinfunction "DRAIN2_P$5") (pintype "bidirectional"))
      (node (ref "LED_GREEN_2") (pin "3") (pinfunction "3_3") (pintype "passive"))
    )
    (net (code "151") (name "Net-(IC5-DRAIN3)") (class "Default")
      (node (ref "IC5") (pin "P$6") (pinfunction "DRAIN3_P$6") (pintype "bidirectional"))
      (node (ref "LED_GREEN_2") (pin "4") (pinfunction "4_4") (pintype "passive"))
    )
    (net (code "152") (name "Net-(IC5-DRAIN4)") (class "Default")
      (node (ref "IC5") (pin "P$7") (pinfunction "DRAIN4_P$7") (pintype "bidirectional"))
      (node (ref "LED_GREEN_2") (pin "5") (pinfunction "5_5") (pintype "passive"))
    )
    (net (code "153") (name "Net-(IC5-DRAIN5)") (class "Default")
      (node (ref "IC5") (pin "P$8") (pinfunction "DRAIN5_P$8") (pintype "bidirectional"))
      (node (ref "LED_GREEN_2") (pin "6") (pinfunction "6_6") (pintype "passive"))
    )
    (net (code "154") (name "Net-(IC5-DRAIN6)") (class "Default")
      (node (ref "IC5") (pin "P$13") (pinfunction "DRAIN6_P$13") (pintype "bidirectional"))
      (node (ref "LED_GREEN_2") (pin "7") (pinfunction "7_7") (pintype "passive"))
    )
    (net (code "155") (name "Net-(IC5-DRAIN7)") (class "Default")
      (node (ref "IC5") (pin "P$14") (pinfunction "DRAIN7_P$14") (pintype "bidirectional"))
      (node (ref "LED_GREEN_2") (pin "8") (pinfunction "8_8") (pintype "passive"))
    )
    (net (code "156") (name "Net-(IC5-DRAIN8)") (class "Default")
      (node (ref "IC5") (pin "P$15") (pinfunction "DRAIN8_P$15") (pintype "bidirectional"))
      (node (ref "LED_GREEN_2") (pin "9") (pinfunction "9_9") (pintype "passive"))
    )
    (net (code "157") (name "Net-(IC5-DRAIN9)") (class "Default")
      (node (ref "IC5") (pin "P$16") (pinfunction "DRAIN9_P$16") (pintype "bidirectional"))
      (node (ref "LED_GREEN_2") (pin "10") (pinfunction "10_10") (pintype "passive"))
    )
    (net (code "158") (name "Net-(IC5-DRAIN10)") (class "Default")
      (node (ref "IC5") (pin "P$17") (pinfunction "DRAIN10_P$17") (pintype "bidirectional"))
      (node (ref "LED_GREEN_2") (pin "11") (pinfunction "11_11") (pintype "passive"))
    )
    (net (code "159") (name "Net-(IC5-DRAIN11)") (class "Default")
      (node (ref "IC5") (pin "P$18") (pinfunction "DRAIN11_P$18") (pintype "bidirectional"))
      (node (ref "LED_GREEN_2") (pin "12") (pinfunction "12_12") (pintype "passive"))
    )
    (net (code "160") (name "Net-(IC5-SER_OUT)") (class "Default")
      (node (ref "IC5") (pin "P$11") (pinfunction "SER_OUT_P$11") (pintype "bidirectional"))
      (node (ref "IC6") (pin "P$2") (pinfunction "SER_IN_P$2") (pintype "bidirectional"))
    )
    (net (code "161") (name "Net-(IC6-DRAIN0)") (class "Default")
      (node (ref "IC6") (pin "P$3") (pinfunction "DRAIN0_P$3") (pintype "bidirectional"))
      (node (ref "LED_BLUE_2") (pin "1") (pinfunction "1_1") (pintype "passive"))
    )
    (net (code "162") (name "Net-(IC6-DRAIN1)") (class "Default")
      (node (ref "IC6") (pin "P$4") (pinfunction "DRAIN1_P$4") (pintype "bidirectional"))
      (node (ref "LED_BLUE_2") (pin "2") (pinfunction "2_2") (pintype "passive"))
    )
    (net (code "163") (name "Net-(IC6-DRAIN2)") (class "Default")
      (node (ref "IC6") (pin "P$5") (pinfunction "DRAIN2_P$5") (pintype "bidirectional"))
      (node (ref "LED_BLUE_2") (pin "3") (pinfunction "3_3") (pintype "passive"))
    )
    (net (code "164") (name "Net-(IC6-DRAIN3)") (class "Default")
      (node (ref "IC6") (pin "P$6") (pinfunction "DRAIN3_P$6") (pintype "bidirectional"))
      (node (ref "LED_BLUE_2") (pin "4") (pinfunction "4_4") (pintype "passive"))
    )
    (net (code "165") (name "Net-(IC6-DRAIN4)") (class "Default")
      (node (ref "IC6") (pin "P$7") (pinfunction "DRAIN4_P$7") (pintype "bidirectional"))
      (node (ref "LED_BLUE_2") (pin "5") (pinfunction "5_5") (pintype "passive"))
    )
    (net (code "166") (name "Net-(IC6-DRAIN5)") (class "Default")
      (node (ref "IC6") (pin "P$8") (pinfunction "DRAIN5_P$8") (pintype "bidirectional"))
      (node (ref "LED_BLUE_2") (pin "6") (pinfunction "6_6") (pintype "passive"))
    )
    (net (code "167") (name "Net-(IC6-DRAIN6)") (class "Default")
      (node (ref "IC6") (pin "P$13") (pinfunction "DRAIN6_P$13") (pintype "bidirectional"))
      (node (ref "LED_BLUE_2") (pin "7") (pinfunction "7_7") (pintype "passive"))
    )
    (net (code "168") (name "Net-(IC6-DRAIN7)") (class "Default")
      (node (ref "IC6") (pin "P$14") (pinfunction "DRAIN7_P$14") (pintype "bidirectional"))
      (node (ref "LED_BLUE_2") (pin "8") (pinfunction "8_8") (pintype "passive"))
    )
    (net (code "169") (name "Net-(IC6-DRAIN8)") (class "Default")
      (node (ref "IC6") (pin "P$15") (pinfunction "DRAIN8_P$15") (pintype "bidirectional"))
      (node (ref "LED_BLUE_2") (pin "9") (pinfunction "9_9") (pintype "passive"))
    )
    (net (code "170") (name "Net-(IC6-DRAIN9)") (class "Default")
      (node (ref "IC6") (pin "P$16") (pinfunction "DRAIN9_P$16") (pintype "bidirectional"))
      (node (ref "LED_BLUE_2") (pin "10") (pinfunction "10_10") (pintype "passive"))
    )
    (net (code "171") (name "Net-(IC6-DRAIN10)") (class "Default")
      (node (ref "IC6") (pin "P$17") (pinfunction "DRAIN10_P$17") (pintype "bidirectional"))
      (node (ref "LED_BLUE_2") (pin "11") (pinfunction "11_11") (pintype "passive"))
    )
    (net (code "172") (name "Net-(IC6-DRAIN11)") (class "Default")
      (node (ref "IC6") (pin "P$18") (pinfunction "DRAIN11_P$18") (pintype "bidirectional"))
      (node (ref "LED_BLUE_2") (pin "12") (pinfunction "12_12") (pintype "passive"))
    )
    (net (code "173") (name "Net-(IC7-DRAIN0)") (class "Default")
      (node (ref "IC7") (pin "P$3") (pinfunction "DRAIN0_P$3") (pintype "bidirectional"))
      (node (ref "LED_RED_3") (pin "1") (pinfunction "1_1") (pintype "passive"))
    )
    (net (code "174") (name "Net-(IC7-DRAIN1)") (class "Default")
      (node (ref "IC7") (pin "P$4") (pinfunction "DRAIN1_P$4") (pintype "bidirectional"))
      (node (ref "LED_RED_3") (pin "2") (pinfunction "2_2") (pintype "passive"))
    )
    (net (code "175") (name "Net-(IC7-DRAIN2)") (class "Default")
      (node (ref "IC7") (pin "P$5") (pinfunction "DRAIN2_P$5") (pintype "bidirectional"))
      (node (ref "LED_RED_3") (pin "3") (pinfunction "3_3") (pintype "passive"))
    )
    (net (code "176") (name "Net-(IC7-DRAIN3)") (class "Default")
      (node (ref "IC7") (pin "P$6") (pinfunction "DRAIN3_P$6") (pintype "bidirectional"))
      (node (ref "LED_RED_3") (pin "4") (pinfunction "4_4") (pintype "passive"))
    )
    (net (code "177") (name "Net-(IC7-DRAIN4)") (class "Default")
      (node (ref "IC7") (pin "P$7") (pinfunction "DRAIN4_P$7") (pintype "bidirectional"))
      (node (ref "LED_RED_3") (pin "5") (pinfunction "5_5") (pintype "passive"))
    )
    (net (code "178") (name "Net-(IC7-DRAIN5)") (class "Default")
      (node (ref "IC7") (pin "P$8") (pinfunction "DRAIN5_P$8") (pintype "bidirectional"))
      (node (ref "LED_RED_3") (pin "6") (pinfunction "6_6") (pintype "passive"))
    )
    (net (code "179") (name "Net-(IC7-DRAIN6)") (class "Default")
      (node (ref "IC7") (pin "P$13") (pinfunction "DRAIN6_P$13") (pintype "bidirectional"))
      (node (ref "LED_RED_3") (pin "7") (pinfunction "7_7") (pintype "passive"))
    )
    (net (code "180") (name "Net-(IC7-DRAIN7)") (class "Default")
      (node (ref "IC7") (pin "P$14") (pinfunction "DRAIN7_P$14") (pintype "bidirectional"))
      (node (ref "LED_RED_3") (pin "8") (pinfunction "8_8") (pintype "passive"))
    )
    (net (code "181") (name "Net-(IC7-DRAIN8)") (class "Default")
      (node (ref "IC7") (pin "P$15") (pinfunction "DRAIN8_P$15") (pintype "bidirectional"))
      (node (ref "LED_RED_3") (pin "9") (pinfunction "9_9") (pintype "passive"))
    )
    (net (code "182") (name "Net-(IC7-DRAIN9)") (class "Default")
      (node (ref "IC7") (pin "P$16") (pinfunction "DRAIN9_P$16") (pintype "bidirectional"))
      (node (ref "LED_RED_3") (pin "10") (pinfunction "10_10") (pintype "passive"))
    )
    (net (code "183") (name "Net-(IC7-DRAIN10)") (class "Default")
      (node (ref "IC7") (pin "P$17") (pinfunction "DRAIN10_P$17") (pintype "bidirectional"))
      (node (ref "LED_RED_3") (pin "11") (pinfunction "11_11") (pintype "passive"))
    )
    (net (code "184") (name "Net-(IC7-DRAIN11)") (class "Default")
      (node (ref "IC7") (pin "P$18") (pinfunction "DRAIN11_P$18") (pintype "bidirectional"))
      (node (ref "LED_RED_3") (pin "12") (pinfunction "12_12") (pintype "passive"))
    )
    (net (code "185") (name "Net-(IC7-SER_OUT)") (class "Default")
      (node (ref "IC7") (pin "P$11") (pinfunction "SER_OUT_P$11") (pintype "bidirectional"))
      (node (ref "IC8") (pin "P$2") (pinfunction "SER_IN_P$2") (pintype "bidirectional"))
    )
    (net (code "186") (name "Net-(IC8-DRAIN0)") (class "Default")
      (node (ref "IC8") (pin "P$3") (pinfunction "DRAIN0_P$3") (pintype "bidirectional"))
      (node (ref "LED_GREEN_3") (pin "1") (pinfunction "1_1") (pintype "passive"))
    )
    (net (code "187") (name "Net-(IC8-DRAIN1)") (class "Default")
      (node (ref "IC8") (pin "P$4") (pinfunction "DRAIN1_P$4") (pintype "bidirectional"))
      (node (ref "LED_GREEN_3") (pin "2") (pinfunction "2_2") (pintype "passive"))
    )
    (net (code "188") (name "Net-(IC8-DRAIN2)") (class "Default")
      (node (ref "IC8") (pin "P$5") (pinfunction "DRAIN2_P$5") (pintype "bidirectional"))
      (node (ref "LED_GREEN_3") (pin "3") (pinfunction "3_3") (pintype "passive"))
    )
    (net (code "189") (name "Net-(IC8-DRAIN3)") (class "Default")
      (node (ref "IC8") (pin "P$6") (pinfunction "DRAIN3_P$6") (pintype "bidirectional"))
      (node (ref "LED_GREEN_3") (pin "4") (pinfunction "4_4") (pintype "passive"))
    )
    (net (code "190") (name "Net-(IC8-DRAIN4)") (class "Default")
      (node (ref "IC8") (pin "P$7") (pinfunction "DRAIN4_P$7") (pintype "bidirectional"))
      (node (ref "LED_GREEN_3") (pin "5") (pinfunction "5_5") (pintype "passive"))
    )
    (net (code "191") (name "Net-(IC8-DRAIN5)") (class "Default")
      (node (ref "IC8") (pin "P$8") (pinfunction "DRAIN5_P$8") (pintype "bidirectional"))
      (node (ref "LED_GREEN_3") (pin "6") (pinfunction "6_6") (pintype "passive"))
    )
    (net (code "192") (name "Net-(IC8-DRAIN6)") (class "Default")
      (node (ref "IC8") (pin "P$13") (pinfunction "DRAIN6_P$13") (pintype "bidirectional"))
      (node (ref "LED_GREEN_3") (pin "7") (pinfunction "7_7") (pintype "passive"))
    )
    (net (code "193") (name "Net-(IC8-DRAIN7)") (class "Default")
      (node (ref "IC8") (pin "P$14") (pinfunction "DRAIN7_P$14") (pintype "bidirectional"))
      (node (ref "LED_GREEN_3") (pin "8") (pinfunction "8_8") (pintype "passive"))
    )
    (net (code "194") (name "Net-(IC8-DRAIN8)") (class "Default")
      (node (ref "IC8") (pin "P$15") (pinfunction "DRAIN8_P$15") (pintype "bidirectional"))
      (node (ref "LED_GREEN_3") (pin "9") (pinfunction "9_9") (pintype "passive"))
    )
    (net (code "195") (name "Net-(IC8-DRAIN9)") (class "Default")
      (node (ref "IC8") (pin "P$16") (pinfunction "DRAIN9_P$16") (pintype "bidirectional"))
      (node (ref "LED_GREEN_3") (pin "10") (pinfunction "10_10") (pintype "passive"))
    )
    (net (code "196") (name "Net-(IC8-DRAIN10)") (class "Default")
      (node (ref "IC8") (pin "P$17") (pinfunction "DRAIN10_P$17") (pintype "bidirectional"))
      (node (ref "LED_GREEN_3") (pin "11") (pinfunction "11_11") (pintype "passive"))
    )
    (net (code "197") (name "Net-(IC8-DRAIN11)") (class "Default")
      (node (ref "IC8") (pin "P$18") (pinfunction "DRAIN11_P$18") (pintype "bidirectional"))
      (node (ref "LED_GREEN_3") (pin "12") (pinfunction "12_12") (pintype "passive"))
    )
    (net (code "198") (name "Net-(IC8-SER_OUT)") (class "Default")
      (node (ref "IC8") (pin "P$11") (pinfunction "SER_OUT_P$11") (pintype "bidirectional"))
      (node (ref "IC9") (pin "P$2") (pinfunction "SER_IN_P$2") (pintype "bidirectional"))
    )
    (net (code "199") (name "Net-(IC9-DRAIN0)") (class "Default")
      (node (ref "IC9") (pin "P$3") (pinfunction "DRAIN0_P$3") (pintype "bidirectional"))
      (node (ref "LED_BLUE_3") (pin "1") (pinfunction "1_1") (pintype "passive"))
    )
    (net (code "200") (name "Net-(IC9-DRAIN1)") (class "Default")
      (node (ref "IC9") (pin "P$4") (pinfunction "DRAIN1_P$4") (pintype "bidirectional"))
      (node (ref "LED_BLUE_3") (pin "2") (pinfunction "2_2") (pintype "passive"))
    )
    (net (code "201") (name "Net-(IC9-DRAIN2)") (class "Default")
      (node (ref "IC9") (pin "P$5") (pinfunction "DRAIN2_P$5") (pintype "bidirectional"))
      (node (ref "LED_BLUE_3") (pin "3") (pinfunction "3_3") (pintype "passive"))
    )
    (net (code "202") (name "Net-(IC9-DRAIN3)") (class "Default")
      (node (ref "IC9") (pin "P$6") (pinfunction "DRAIN3_P$6") (pintype "bidirectional"))
      (node (ref "LED_BLUE_3") (pin "4") (pinfunction "4_4") (pintype "passive"))
    )
    (net (code "203") (name "Net-(IC9-DRAIN4)") (class "Default")
      (node (ref "IC9") (pin "P$7") (pinfunction "DRAIN4_P$7") (pintype "bidirectional"))
      (node (ref "LED_BLUE_3") (pin "5") (pinfunction "5_5") (pintype "passive"))
    )
    (net (code "204") (name "Net-(IC9-DRAIN5)") (class "Default")
      (node (ref "IC9") (pin "P$8") (pinfunction "DRAIN5_P$8") (pintype "bidirectional"))
      (node (ref "LED_BLUE_3") (pin "6") (pinfunction "6_6") (pintype "passive"))
    )
    (net (code "205") (name "Net-(IC9-DRAIN6)") (class "Default")
      (node (ref "IC9") (pin "P$13") (pinfunction "DRAIN6_P$13") (pintype "bidirectional"))
      (node (ref "LED_BLUE_3") (pin "7") (pinfunction "7_7") (pintype "passive"))
    )
    (net (code "206") (name "Net-(IC9-DRAIN7)") (class "Default")
      (node (ref "IC9") (pin "P$14") (pinfunction "DRAIN7_P$14") (pintype "bidirectional"))
      (node (ref "LED_BLUE_3") (pin "8") (pinfunction "8_8") (pintype "passive"))
    )
    (net (code "207") (name "Net-(IC9-DRAIN8)") (class "Default")
      (node (ref "IC9") (pin "P$15") (pinfunction "DRAIN8_P$15") (pintype "bidirectional"))
      (node (ref "LED_BLUE_3") (pin "9") (pinfunction "9_9") (pintype "passive"))
    )
    (net (code "208") (name "Net-(IC9-DRAIN9)") (class "Default")
      (node (ref "IC9") (pin "P$16") (pinfunction "DRAIN9_P$16") (pintype "bidirectional"))
      (node (ref "LED_BLUE_3") (pin "10") (pinfunction "10_10") (pintype "passive"))
    )
    (net (code "209") (name "Net-(IC9-DRAIN10)") (class "Default")
      (node (ref "IC9") (pin "P$17") (pinfunction "DRAIN10_P$17") (pintype "bidirectional"))
      (node (ref "LED_BLUE_3") (pin "11") (pinfunction "11_11") (pintype "passive"))
    )
    (net (code "210") (name "Net-(IC9-DRAIN11)") (class "Default")
      (node (ref "IC9") (pin "P$18") (pinfunction "DRAIN11_P$18") (pintype "bidirectional"))
      (node (ref "LED_BLUE_3") (pin "12") (pinfunction "12_12") (pintype "passive"))
    )
    (net (code "211") (name "Net-(IC10-DRAIN0)") (class "Default")
      (node (ref "IC10") (pin "P$3") (pinfunction "DRAIN0_P$3") (pintype "bidirectional"))
      (node (ref "LED_RED_4") (pin "1") (pinfunction "1_1") (pintype "passive"))
    )
    (net (code "212") (name "Net-(IC10-DRAIN1)") (class "Default")
      (node (ref "IC10") (pin "P$4") (pinfunction "DRAIN1_P$4") (pintype "bidirectional"))
      (node (ref "LED_RED_4") (pin "2") (pinfunction "2_2") (pintype "passive"))
    )
    (net (code "213") (name "Net-(IC10-DRAIN2)") (class "Default")
      (node (ref "IC10") (pin "P$5") (pinfunction "DRAIN2_P$5") (pintype "bidirectional"))
      (node (ref "LED_RED_4") (pin "3") (pinfunction "3_3") (pintype "passive"))
    )
    (net (code "214") (name "Net-(IC10-DRAIN3)") (class "Default")
      (node (ref "IC10") (pin "P$6") (pinfunction "DRAIN3_P$6") (pintype "bidirectional"))
      (node (ref "LED_RED_4") (pin "4") (pinfunction "4_4") (pintype "passive"))
    )
    (net (code "215") (name "Net-(IC10-DRAIN4)") (class "Default")
      (node (ref "IC10") (pin "P$7") (pinfunction "DRAIN4_P$7") (pintype "bidirectional"))
      (node (ref "LED_RED_4") (pin "5") (pinfunction "5_5") (pintype "passive"))
    )
    (net (code "216") (name "Net-(IC10-DRAIN5)") (class "Default")
      (node (ref "IC10") (pin "P$8") (pinfunction "DRAIN5_P$8") (pintype "bidirectional"))
      (node (ref "LED_RED_4") (pin "6") (pinfunction "6_6") (pintype "passive"))
    )
    (net (code "217") (name "Net-(IC10-DRAIN6)") (class "Default")
      (node (ref "IC10") (pin "P$13") (pinfunction "DRAIN6_P$13") (pintype "bidirectional"))
      (node (ref "LED_RED_4") (pin "7") (pinfunction "7_7") (pintype "passive"))
    )
    (net (code "218") (name "Net-(IC10-DRAIN7)") (class "Default")
      (node (ref "IC10") (pin "P$14") (pinfunction "DRAIN7_P$14") (pintype "bidirectional"))
      (node (ref "LED_RED_4") (pin "8") (pinfunction "8_8") (pintype "passive"))
    )
    (net (code "219") (name "Net-(IC10-DRAIN8)") (class "Default")
      (node (ref "IC10") (pin "P$15") (pinfunction "DRAIN8_P$15") (pintype "bidirectional"))
      (node (ref "LED_RED_4") (pin "9") (pinfunction "9_9") (pintype "passive"))
    )
    (net (code "220") (name "Net-(IC10-DRAIN9)") (class "Default")
      (node (ref "IC10") (pin "P$16") (pinfunction "DRAIN9_P$16") (pintype "bidirectional"))
      (node (ref "LED_RED_4") (pin "10") (pinfunction "10_10") (pintype "passive"))
    )
    (net (code "221") (name "Net-(IC10-DRAIN10)") (class "Default")
      (node (ref "IC10") (pin "P$17") (pinfunction "DRAIN10_P$17") (pintype "bidirectional"))
      (node (ref "LED_RED_4") (pin "11") (pinfunction "11_11") (pintype "passive"))
    )
    (net (code "222") (name "Net-(IC10-DRAIN11)") (class "Default")
      (node (ref "IC10") (pin "P$18") (pinfunction "DRAIN11_P$18") (pintype "bidirectional"))
      (node (ref "LED_RED_4") (pin "12") (pinfunction "12_12") (pintype "passive"))
    )
    (net (code "223") (name "Net-(IC10-SER_OUT)") (class "Default")
      (node (ref "IC10") (pin "P$11") (pinfunction "SER_OUT_P$11") (pintype "bidirectional"))
      (node (ref "IC11") (pin "P$2") (pinfunction "SER_IN_P$2") (pintype "bidirectional"))
    )
    (net (code "224") (name "Net-(IC11-DRAIN0)") (class "Default")
      (node (ref "IC11") (pin "P$3") (pinfunction "DRAIN0_P$3") (pintype "bidirectional"))
      (node (ref "LED_GREEN_4") (pin "1") (pinfunction "1_1") (pintype "passive"))
    )
    (net (code "225") (name "Net-(IC11-DRAIN1)") (class "Default")
      (node (ref "IC11") (pin "P$4") (pinfunction "DRAIN1_P$4") (pintype "bidirectional"))
      (node (ref "LED_GREEN_4") (pin "2") (pinfunction "2_2") (pintype "passive"))
    )
    (net (code "226") (name "Net-(IC11-DRAIN2)") (class "Default")
      (node (ref "IC11") (pin "P$5") (pinfunction "DRAIN2_P$5") (pintype "bidirectional"))
      (node (ref "LED_GREEN_4") (pin "3") (pinfunction "3_3") (pintype "passive"))
    )
    (net (code "227") (name "Net-(IC11-DRAIN3)") (class "Default")
      (node (ref "IC11") (pin "P$6") (pinfunction "DRAIN3_P$6") (pintype "bidirectional"))
      (node (ref "LED_GREEN_4") (pin "4") (pinfunction "4_4") (pintype "passive"))
    )
    (net (code "228") (name "Net-(IC11-DRAIN4)") (class "Default")
      (node (ref "IC11") (pin "P$7") (pinfunction "DRAIN4_P$7") (pintype "bidirectional"))
      (node (ref "LED_GREEN_4") (pin "5") (pinfunction "5_5") (pintype "passive"))
    )
    (net (code "229") (name "Net-(IC11-DRAIN5)") (class "Default")
      (node (ref "IC11") (pin "P$8") (pinfunction "DRAIN5_P$8") (pintype "bidirectional"))
      (node (ref "LED_GREEN_4") (pin "6") (pinfunction "6_6") (pintype "passive"))
    )
    (net (code "230") (name "Net-(IC11-DRAIN6)") (class "Default")
      (node (ref "IC11") (pin "P$13") (pinfunction "DRAIN6_P$13") (pintype "bidirectional"))
      (node (ref "LED_GREEN_4") (pin "7") (pinfunction "7_7") (pintype "passive"))
    )
    (net (code "231") (name "Net-(IC11-DRAIN7)") (class "Default")
      (node (ref "IC11") (pin "P$14") (pinfunction "DRAIN7_P$14") (pintype "bidirectional"))
      (node (ref "LED_GREEN_4") (pin "8") (pinfunction "8_8") (pintype "passive"))
    )
    (net (code "232") (name "Net-(IC11-DRAIN8)") (class "Default")
      (node (ref "IC11") (pin "P$15") (pinfunction "DRAIN8_P$15") (pintype "bidirectional"))
      (node (ref "LED_GREEN_4") (pin "9") (pinfunction "9_9") (pintype "passive"))
    )
    (net (code "233") (name "Net-(IC11-DRAIN9)") (class "Default")
      (node (ref "IC11") (pin "P$16") (pinfunction "DRAIN9_P$16") (pintype "bidirectional"))
      (node (ref "LED_GREEN_4") (pin "10") (pinfunction "10_10") (pintype "passive"))
    )
    (net (code "234") (name "Net-(IC11-DRAIN10)") (class "Default")
      (node (ref "IC11") (pin "P$17") (pinfunction "DRAIN10_P$17") (pintype "bidirectional"))
      (node (ref "LED_GREEN_4") (pin "11") (pinfunction "11_11") (pintype "passive"))
    )
    (net (code "235") (name "Net-(IC11-DRAIN11)") (class "Default")
      (node (ref "IC11") (pin "P$18") (pinfunction "DRAIN11_P$18") (pintype "bidirectional"))
      (node (ref "LED_GREEN_4") (pin "12") (pinfunction "12_12") (pintype "passive"))
    )
    (net (code "236") (name "Net-(IC11-SER_OUT)") (class "Default")
      (node (ref "IC11") (pin "P$11") (pinfunction "SER_OUT_P$11") (pintype "bidirectional"))
      (node (ref "IC12") (pin "P$2") (pinfunction "SER_IN_P$2") (pintype "bidirectional"))
    )
    (net (code "237") (name "Net-(IC12-DRAIN0)") (class "Default")
      (node (ref "IC12") (pin "P$3") (pinfunction "DRAIN0_P$3") (pintype "bidirectional"))
      (node (ref "LED_BLUE_4") (pin "1") (pinfunction "1_1") (pintype "passive"))
    )
    (net (code "238") (name "Net-(IC12-DRAIN1)") (class "Default")
      (node (ref "IC12") (pin "P$4") (pinfunction "DRAIN1_P$4") (pintype "bidirectional"))
      (node (ref "LED_BLUE_4") (pin "2") (pinfunction "2_2") (pintype "passive"))
    )
    (net (code "239") (name "Net-(IC12-DRAIN2)") (class "Default")
      (node (ref "IC12") (pin "P$5") (pinfunction "DRAIN2_P$5") (pintype "bidirectional"))
      (node (ref "LED_BLUE_4") (pin "3") (pinfunction "3_3") (pintype "passive"))
    )
    (net (code "240") (name "Net-(IC12-DRAIN3)") (class "Default")
      (node (ref "IC12") (pin "P$6") (pinfunction "DRAIN3_P$6") (pintype "bidirectional"))
      (node (ref "LED_BLUE_4") (pin "4") (pinfunction "4_4") (pintype "passive"))
    )
    (net (code "241") (name "Net-(IC12-DRAIN4)") (class "Default")
      (node (ref "IC12") (pin "P$7") (pinfunction "DRAIN4_P$7") (pintype "bidirectional"))
      (node (ref "LED_BLUE_4") (pin "5") (pinfunction "5_5") (pintype "passive"))
    )
    (net (code "242") (name "Net-(IC12-DRAIN5)") (class "Default")
      (node (ref "IC12") (pin "P$8") (pinfunction "DRAIN5_P$8") (pintype "bidirectional"))
      (node (ref "LED_BLUE_4") (pin "6") (pinfunction "6_6") (pintype "passive"))
    )
    (net (code "243") (name "Net-(IC12-DRAIN6)") (class "Default")
      (node (ref "IC12") (pin "P$13") (pinfunction "DRAIN6_P$13") (pintype "bidirectional"))
      (node (ref "LED_BLUE_4") (pin "7") (pinfunction "7_7") (pintype "passive"))
    )
    (net (code "244") (name "Net-(IC12-DRAIN7)") (class "Default")
      (node (ref "IC12") (pin "P$14") (pinfunction "DRAIN7_P$14") (pintype "bidirectional"))
      (node (ref "LED_BLUE_4") (pin "8") (pinfunction "8_8") (pintype "passive"))
    )
    (net (code "245") (name "Net-(IC12-DRAIN8)") (class "Default")
      (node (ref "IC12") (pin "P$15") (pinfunction "DRAIN8_P$15") (pintype "bidirectional"))
      (node (ref "LED_BLUE_4") (pin "9") (pinfunction "9_9") (pintype "passive"))
    )
    (net (code "246") (name "Net-(IC12-DRAIN9)") (class "Default")
      (node (ref "IC12") (pin "P$16") (pinfunction "DRAIN9_P$16") (pintype "bidirectional"))
      (node (ref "LED_BLUE_4") (pin "10") (pinfunction "10_10") (pintype "passive"))
    )
    (net (code "247") (name "Net-(IC12-DRAIN10)") (class "Default")
      (node (ref "IC12") (pin "P$17") (pinfunction "DRAIN10_P$17") (pintype "bidirectional"))
      (node (ref "LED_BLUE_4") (pin "11") (pinfunction "11_11") (pintype "passive"))
    )
    (net (code "248") (name "Net-(IC12-DRAIN11)") (class "Default")
      (node (ref "IC12") (pin "P$18") (pinfunction "DRAIN11_P$18") (pintype "bidirectional"))
      (node (ref "LED_BLUE_4") (pin "12") (pinfunction "12_12") (pintype "passive"))
    )
    (net (code "249") (name "Net-(R1-Pad2)") (class "Default")
      (node (ref "R1") (pin "2") (pinfunction "2_2") (pintype "passive"))
      (node (ref "R2") (pin "2") (pinfunction "2_2") (pintype "passive"))
      (node (ref "SENSE_1") (pin "1") (pinfunction "1_1") (pintype "passive"))
    )
    (net (code "250") (name "Net-(R3-Pad2)") (class "Default")
      (node (ref "R3") (pin "2") (pinfunction "2_2") (pintype "passive"))
      (node (ref "R4") (pin "2") (pinfunction "2_2") (pintype "passive"))
      (node (ref "SENSE_1") (pin "2") (pinfunction "2_2") (pintype "passive"))
    )
    (net (code "251") (name "Net-(R5-Pad2)") (class "Default")
      (node (ref "R5") (pin "2") (pinfunction "2_2") (pintype "passive"))
      (node (ref "R6") (pin "2") (pinfunction "2_2") (pintype "passive"))
      (node (ref "SENSE_1") (pin "3") (pinfunction "3_3") (pintype "passive"))
    )
    (net (code "252") (name "Net-(R7-Pad2)") (class "Default")
      (node (ref "R7") (pin "2") (pinfunction "2_2") (pintype "passive"))
      (node (ref "R8") (pin "2") (pinfunction "2_2") (pintype "passive"))
      (node (ref "SENSE_1") (pin "4") (pinfunction "4_4") (pintype "passive"))
    )
    (net (code "253") (name "Net-(R10-Pad2)") (class "Default")
      (node (ref "R10") (pin "2") (pinfunction "2_2") (pintype "passive"))
      (node (ref "R9") (pin "2") (pinfunction "2_2") (pintype "passive"))
      (node (ref "SENSE_1") (pin "5") (pinfunction "5_5") (pintype "passive"))
    )
    (net (code "254") (name "Net-(R11-Pad2)") (class "Default")
      (node (ref "R11") (pin "2") (pinfunction "2_2") (pintype "passive"))
      (node (ref "R12") (pin "2") (pinfunction "2_2") (pintype "passive"))
      (node (ref "SENSE_1") (pin "6") (pinfunction "6_6") (pintype "passive"))
    )
    (net (code "255") (name "Net-(R13-Pad2)") (class "Default")
      (node (ref "R13") (pin "2") (pinfunction "2_2") (pintype "passive"))
      (node (ref "R14") (pin "2") (pinfunction "2_2") (pintype "passive"))
      (node (ref "SENSE_1") (pin "7") (pinfunction "7_7") (pintype "passive"))
    )
    (net (code "256") (name "Net-(R15-Pad2)") (class "Default")
      (node (ref "R15") (pin "2") (pinfunction "2_2") (pintype "passive"))
      (node (ref "R16") (pin "2") (pinfunction "2_2") (pintype "passive"))
      (node (ref "SENSE_1") (pin "8") (pinfunction "8_8") (pintype "passive"))
    )
    (net (code "257") (name "Net-(R17-Pad2)") (class "Default")
      (node (ref "R17") (pin "2") (pinfunction "2_2") (pintype "passive"))
      (node (ref "R18") (pin "2") (pinfunction "2_2") (pintype "passive"))
      (node (ref "SENSE_1") (pin "9") (pinfunction "9_9") (pintype "passive"))
    )
    (net (code "258") (name "Net-(R19-Pad2)") (class "Default")
      (node (ref "R19") (pin "2") (pinfunction "2_2") (pintype "passive"))
      (node (ref "R20") (pin "2") (pinfunction "2_2") (pintype "passive"))
      (node (ref "SENSE_1") (pin "10") (pinfunction "10_10") (pintype "passive"))
    )
    (net (code "259") (name "Net-(R21-Pad2)") (class "Default")
      (node (ref "R21") (pin "2") (pinfunction "2_2") (pintype "passive"))
      (node (ref "R22") (pin "2") (pinfunction "2_2") (pintype "passive"))
      (node (ref "SENSE_1") (pin "11") (pinfunction "11_11") (pintype "passive"))
    )
    (net (code "260") (name "Net-(R23-Pad2)") (class "Default")
      (node (ref "R23") (pin "2") (pinfunction "2_2") (pintype "passive"))
      (node (ref "R24") (pin "2") (pinfunction "2_2") (pintype "passive"))
      (node (ref "SENSE_1") (pin "12") (pinfunction "12_12") (pintype "passive"))
    )
    (net (code "261") (name "Net-(R25-Pad2)") (class "Default")
      (node (ref "R25") (pin "2") (pinfunction "2_2") (pintype "passive"))
      (node (ref "R26") (pin "2") (pinfunction "2_2") (pintype "passive"))
      (node (ref "SENSE_2") (pin "1") (pinfunction "1_1") (pintype "passive"))
    )
    (net (code "262") (name "Net-(R27-Pad2)") (class "Default")
      (node (ref "R27") (pin "2") (pinfunction "2_2") (pintype "passive"))
      (node (ref "R28") (pin "2") (pinfunction "2_2") (pintype "passive"))
      (node (ref "SENSE_2") (pin "2") (pinfunction "2_2") (pintype "passive"))
    )
    (net (code "263") (name "Net-(R29-Pad2)") (class "Default")
      (node (ref "R29") (pin "2") (pinfunction "2_2") (pintype "passive"))
      (node (ref "R30") (pin "2") (pinfunction "2_2") (pintype "passive"))
      (node (ref "SENSE_2") (pin "3") (pinfunction "3_3") (pintype "passive"))
    )
    (net (code "264") (name "Net-(R31-Pad2)") (class "Default")
      (node (ref "R31") (pin "2") (pinfunction "2_2") (pintype "passive"))
      (node (ref "R32") (pin "2") (pinfunction "2_2") (pintype "passive"))
      (node (ref "SENSE_2") (pin "4") (pinfunction "4_4") (pintype "passive"))
    )
    (net (code "265") (name "Net-(R33-Pad2)") (class "Default")
      (node (ref "R33") (pin "2") (pinfunction "2_2") (pintype "passive"))
      (node (ref "R34") (pin "2") (pinfunction "2_2") (pintype "passive"))
      (node (ref "SENSE_2") (pin "5") (pinfunction "5_5") (pintype "passive"))
    )
    (net (code "266") (name "Net-(R35-Pad2)") (class "Default")
      (node (ref "R35") (pin "2") (pinfunction "2_2") (pintype "passive"))
      (node (ref "R36") (pin "2") (pinfunction "2_2") (pintype "passive"))
      (node (ref "SENSE_2") (pin "6") (pinfunction "6_6") (pintype "passive"))
    )
    (net (code "267") (name "Net-(R37-Pad2)") (class "Default")
      (node (ref "R37") (pin "2") (pinfunction "2_2") (pintype "passive"))
      (node (ref "R38") (pin "2") (pinfunction "2_2") (pintype "passive"))
      (node (ref "SENSE_2") (pin "7") (pinfunction "7_7") (pintype "passive"))
    )
    (net (code "268") (name "Net-(R39-Pad2)") (class "Default")
      (node (ref "R39") (pin "2") (pinfunction "2_2") (pintype "passive"))
      (node (ref "R40") (pin "2") (pinfunction "2_2") (pintype "passive"))
      (node (ref "SENSE_2") (pin "8") (pinfunction "8_8") (pintype "passive"))
    )
    (net (code "269") (name "Net-(R41-Pad2)") (class "Default")
      (node (ref "R41") (pin "2") (pinfunction "2_2") (pintype "passive"))
      (node (ref "R42") (pin "2") (pinfunction "2_2") (pintype "passive"))
      (node (ref "SENSE_2") (pin "9") (pinfunction "9_9") (pintype "passive"))
    )
    (net (code "270") (name "Net-(R43-Pad2)") (class "Default")
      (node (ref "R43") (pin "2") (pinfunction "2_2") (pintype "passive"))
      (node (ref "R44") (pin "2") (pinfunction "2_2") (pintype "passive"))
      (node (ref "SENSE_2") (pin "10") (pinfunction "10_10") (pintype "passive"))
    )
    (net (code "271") (name "Net-(R45-Pad2)") (class "Default")
      (node (ref "R45") (pin "2") (pinfunction "2_2") (pintype "passive"))
      (node (ref "R46") (pin "2") (pinfunction "2_2") (pintype "passive"))
      (node (ref "SENSE_2") (pin "11") (pinfunction "11_11") (pintype "passive"))
    )
    (net (code "272") (name "Net-(R47-Pad2)") (class "Default")
      (node (ref "R47") (pin "2") (pinfunction "2_2") (pintype "passive"))
      (node (ref "R48") (pin "2") (pinfunction "2_2") (pintype "passive"))
      (node (ref "SENSE_2") (pin "12") (pinfunction "12_12") (pintype "passive"))
    )
    (net (code "273") (name "Net-(R49-Pad2)") (class "Default")
      (node (ref "R49") (pin "2") (pinfunction "2_2") (pintype "passive"))
      (node (ref "R50") (pin "2") (pinfunction "2_2") (pintype "passive"))
      (node (ref "SENSE_3") (pin "1") (pinfunction "1_1") (pintype "passive"))
    )
    (net (code "274") (name "Net-(R51-Pad2)") (class "Default")
      (node (ref "R51") (pin "2") (pinfunction "2_2") (pintype "passive"))
      (node (ref "R52") (pin "2") (pinfunction "2_2") (pintype "passive"))
      (node (ref "SENSE_3") (pin "2") (pinfunction "2_2") (pintype "passive"))
    )
    (net (code "275") (name "Net-(R53-Pad2)") (class "Default")
      (node (ref "R53") (pin "2") (pinfunction "2_2") (pintype "passive"))
      (node (ref "R54") (pin "2") (pinfunction "2_2") (pintype "passive"))
      (node (ref "SENSE_3") (pin "3") (pinfunction "3_3") (pintype "passive"))
    )
    (net (code "276") (name "Net-(R55-Pad2)") (class "Default")
      (node (ref "R55") (pin "2") (pinfunction "2_2") (pintype "passive"))
      (node (ref "R56") (pin "2") (pinfunction "2_2") (pintype "passive"))
      (node (ref "SENSE_3") (pin "4") (pinfunction "4_4") (pintype "passive"))
    )
    (net (code "277") (name "Net-(R57-Pad2)") (class "Default")
      (node (ref "R57") (pin "2") (pinfunction "2_2") (pintype "passive"))
      (node (ref "R58") (pin "2") (pinfunction "2_2") (pintype "passive"))
      (node (ref "SENSE_3") (pin "5") (pinfunction "5_5") (pintype "passive"))
    )
    (net (code "278") (name "Net-(R59-Pad2)") (class "Default")
      (node (ref "R59") (pin "2") (pinfunction "2_2") (pintype "passive"))
      (node (ref "R60") (pin "2") (pinfunction "2_2") (pintype "passive"))
      (node (ref "SENSE_3") (pin "6") (pinfunction "6_6") (pintype "passive"))
    )
    (net (code "279") (name "Net-(R61-Pad2)") (class "Default")
      (node (ref "R61") (pin "2") (pinfunction "2_2") (pintype "passive"))
      (node (ref "R62") (pin "2") (pinfunction "2_2") (pintype "passive"))
      (node (ref "SENSE_3") (pin "7") (pinfunction "7_7") (pintype "passive"))
    )
    (net (code "280") (name "Net-(R63-Pad2)") (class "Default")
      (node (ref "R63") (pin "2") (pinfunction "2_2") (pintype "passive"))
      (node (ref "R64") (pin "2") (pinfunction "2_2") (pintype "passive"))
      (node (ref "SENSE_3") (pin "8") (pinfunction "8_8") (pintype "passive"))
    )
    (net (code "281") (name "Net-(R65-Pad2)") (class "Default")
      (node (ref "R65") (pin "2") (pinfunction "2_2") (pintype "passive"))
      (node (ref "R66") (pin "2") (pinfunction "2_2") (pintype "passive"))
      (node (ref "SENSE_3") (pin "9") (pinfunction "9_9") (pintype "passive"))
    )
    (net (code "282") (name "Net-(R67-Pad2)") (class "Default")
      (node (ref "R67") (pin "2") (pinfunction "2_2") (pintype "passive"))
      (node (ref "R68") (pin "2") (pinfunction "2_2") (pintype "passive"))
      (node (ref "SENSE_3") (pin "10") (pinfunction "10_10") (pintype "passive"))
    )
    (net (code "283") (name "Net-(R69-Pad2)") (class "Default")
      (node (ref "R69") (pin "2") (pinfunction "2_2") (pintype "passive"))
      (node (ref "R70") (pin "2") (pinfunction "2_2") (pintype "passive"))
      (node (ref "SENSE_3") (pin "11") (pinfunction "11_11") (pintype "passive"))
    )
    (net (code "284") (name "Net-(R71-Pad2)") (class "Default")
      (node (ref "R71") (pin "2") (pinfunction "2_2") (pintype "passive"))
      (node (ref "R72") (pin "2") (pinfunction "2_2") (pintype "passive"))
      (node (ref "SENSE_3") (pin "12") (pinfunction "12_12") (pintype "passive"))
    )
    (net (code "285") (name "Net-(R73-Pad2)") (class "Default")
      (node (ref "R73") (pin "2") (pinfunction "2_2") (pintype "passive"))
      (node (ref "R74") (pin "2") (pinfunction "2_2") (pintype "passive"))
      (node (ref "SENSE_4") (pin "1") (pinfunction "1_1") (pintype "passive"))
    )
    (net (code "286") (name "Net-(R75-Pad2)") (class "Default")
      (node (ref "R75") (pin "2") (pinfunction "2_2") (pintype "passive"))
      (node (ref "R76") (pin "2") (pinfunction "2_2") (pintype "passive"))
      (node (ref "SENSE_4") (pin "2") (pinfunction "2_2") (pintype "passive"))
    )
    (net (code "287") (name "Net-(R77-Pad2)") (class "Default")
      (node (ref "R77") (pin "2") (pinfunction "2_2") (pintype "passive"))
      (node (ref "R78") (pin "2") (pinfunction "2_2") (pintype "passive"))
      (node (ref "SENSE_4") (pin "3") (pinfunction "3_3") (pintype "passive"))
    )
    (net (code "288") (name "Net-(R79-Pad2)") (class "Default")
      (node (ref "R79") (pin "2") (pinfunction "2_2") (pintype "passive"))
      (node (ref "R80") (pin "2") (pinfunction "2_2") (pintype "passive"))
      (node (ref "SENSE_4") (pin "4") (pinfunction "4_4") (pintype "passive"))
    )
    (net (code "289") (name "Net-(R81-Pad2)") (class "Default")
      (node (ref "R81") (pin "2") (pinfunction "2_2") (pintype "passive"))
      (node (ref "R82") (pin "2") (pinfunction "2_2") (pintype "passive"))
      (node (ref "SENSE_4") (pin "5") (pinfunction "5_5") (pintype "passive"))
    )
    (net (code "290") (name "Net-(R83-Pad2)") (class "Default")
      (node (ref "R83") (pin "2") (pinfunction "2_2") (pintype "passive"))
      (node (ref "R84") (pin "2") (pinfunction "2_2") (pintype "passive"))
      (node (ref "SENSE_4") (pin "6") (pinfunction "6_6") (pintype "passive"))
    )
    (net (code "291") (name "Net-(R85-Pad2)") (class "Default")
      (node (ref "R85") (pin "2") (pinfunction "2_2") (pintype "passive"))
      (node (ref "R86") (pin "2") (pinfunction "2_2") (pintype "passive"))
      (node (ref "SENSE_4") (pin "7") (pinfunction "7_7") (pintype "passive"))
    )
    (net (code "292") (name "Net-(R87-Pad2)") (class "Default")
      (node (ref "R87") (pin "2") (pinfunction "2_2") (pintype "passive"))
      (node (ref "R88") (pin "2") (pinfunction "2_2") (pintype "passive"))
      (node (ref "SENSE_4") (pin "8") (pinfunction "8_8") (pintype "passive"))
    )
    (net (code "293") (name "Net-(R89-Pad2)") (class "Default")
      (node (ref "R89") (pin "2") (pinfunction "2_2") (pintype "passive"))
      (node (ref "R90") (pin "2") (pinfunction "2_2") (pintype "passive"))
      (node (ref "SENSE_4") (pin "9") (pinfunction "9_9") (pintype "passive"))
    )
    (net (code "294") (name "Net-(R91-Pad2)") (class "Default")
      (node (ref "R91") (pin "2") (pinfunction "2_2") (pintype "passive"))
      (node (ref "R92") (pin "2") (pinfunction "2_2") (pintype "passive"))
      (node (ref "SENSE_4") (pin "10") (pinfunction "10_10") (pintype "passive"))
    )
    (net (code "295") (name "Net-(R93-Pad2)") (class "Default")
      (node (ref "R93") (pin "2") (pinfunction "2_2") (pintype "passive"))
      (node (ref "R94") (pin "2") (pinfunction "2_2") (pintype "passive"))
      (node (ref "SENSE_4") (pin "11") (pinfunction "11_11") (pintype "passive"))
    )
    (net (code "296") (name "Net-(R95-Pad2)") (class "Default")
      (node (ref "R95") (pin "2") (pinfunction "2_2") (pintype "passive"))
      (node (ref "R96") (pin "2") (pinfunction "2_2") (pintype "passive"))
      (node (ref "SENSE_4") (pin "12") (pinfunction "12_12") (pintype "passive"))
    )
    (net (code "297") (name "unconnected-(IC3-SER_OUT-PadP$11)") (class "Default")
      (node (ref "IC3") (pin "P$11") (pinfunction "SER_OUT_P$11") (pintype "bidirectional"))
    )
    (net (code "298") (name "unconnected-(IC6-SER_OUT-PadP$11)") (class "Default")
      (node (ref "IC6") (pin "P$11") (pinfunction "SER_OUT_P$11") (pintype "bidirectional"))
    )
    (net (code "299") (name "unconnected-(IC9-SER_OUT-PadP$11)") (class "Default")
      (node (ref "IC9") (pin "P$11") (pinfunction "SER_OUT_P$11") (pintype "bidirectional"))
    )
    (net (code "300") (name "unconnected-(IC12-SER_OUT-PadP$11)") (class "Default")
      (node (ref "IC12") (pin "P$11") (pinfunction "SER_OUT_P$11") (pintype "bidirectional"))
    )
    (net (code "301") (name "unconnected-(U1-0(RX0)-Pad0)") (class "Default")
      (node (ref "U1") (pin "0") (pinfunction "0(RX0)_0") (pintype "bidirectional"))
    )
    (net (code "302") (name "unconnected-(U1-1(TX0)-Pad1)") (class "Default")
      (node (ref "U1") (pin "1") (pinfunction "1(TX0)_1") (pintype "bidirectional"))
    )
    (net (code "303") (name "unconnected-(U1-5V-Pad5V@0)") (class "Default")
      (node (ref "U1") (pin "5V@0") (pinfunction "5V_5V@0") (pintype "bidirectional"))
    )
    (net (code "304") (name "unconnected-(U1-5V-Pad5V@1)") (class "Default")
      (node (ref "U1") (pin "5V@1") (pinfunction "5V_5V@1") (pintype "bidirectional"))
    )
    (net (code "305") (name "unconnected-(U1-5V-Pad5V@2)") (class "Default")
      (node (ref "U1") (pin "5V@2") (pinfunction "5V_5V@2") (pintype "bidirectional"))
    )
    (net (code "306") (name "unconnected-(U1-20(SDA)-Pad20)") (class "Default")
      (node (ref "U1") (pin "20") (pinfunction "20(SDA)_20") (pintype "bidirectional"))
    )
    (net (code "307") (name "unconnected-(U1-21(SCL)-Pad21)") (class "Default")
      (node (ref "U1") (pin "21") (pinfunction "21(SCL)_21") (pintype "bidirectional"))
    )
    (net (code "308") (name "unconnected-(U1-Pad3.3V)") (class "Default")
      (node (ref "U1") (pin "3.3V") (pinfunction "3.3V_3.3V") (pintype "bidirectional"))
    )
    (net (code "309") (name "unconnected-(U1-PadAREF)") (class "Default")
      (node (ref "U1") (pin "AREF") (pinfunction "AREF_AREF") (pintype "bidirectional"))
    )
    (net (code "310") (name "unconnected-(U1-PadRESET)") (class "Default")
      (node (ref "U1") (pin "RESET") (pinfunction "RESET_RESET") (pintype "bidirectional"))
    )
    (net (code "311") (name "unconnected-(U2-0(RX0)-Pad0)") (class "Default")
      (node (ref "U2") (pin "0") (pinfunction "0(RX0)_0") (pintype "bidirectional"))
    )
    (net (code "312") (name "unconnected-(U2-1(TX0)-Pad1)") (class "Default")
      (node (ref "U2") (pin "1") (pinfunction "1(TX0)_1") (pintype "bidirectional"))
    )
    (net (code "313") (name "unconnected-(U2-5V-Pad5V@0)") (class "Default")
      (node (ref "U2") (pin "5V@0") (pinfunction "5V_5V@0") (pintype "bidirectional"))
    )
    (net (code "314") (name "unconnected-(U2-5V-Pad5V@1)") (class "Default")
      (node (ref "U2") (pin "5V@1") (pinfunction "5V_5V@1") (pintype "bidirectional"))
    )
    (net (code "315") (name "unconnected-(U2-5V-Pad5V@2)") (class "Default")
      (node (ref "U2") (pin "5V@2") (pinfunction "5V_5V@2") (pintype "bidirectional"))
    )
    (net (code "316") (name "unconnected-(U2-16(TX2)-Pad16)") (class "Default")
      (node (ref "U2") (pin "16") (pinfunction "16(TX2)_16") (pintype "bidirectional"))
    )
    (net (code "317") (name "unconnected-(U2-17(RX2)-Pad17)") (class "Default")
      (node (ref "U2") (pin "17") (pinfunction "17(RX2)_17") (pintype "bidirectional"))
    )
    (net (code "318") (name "unconnected-(U2-18(TX1)-Pad18)") (class "Default")
      (node (ref "U2") (pin "18") (pinfunction "18(TX1)_18") (pintype "bidirectional"))
    )
    (net (code "319") (name "unconnected-(U2-19(RX1)-Pad19)") (class "Default")
      (node (ref "U2") (pin "19") (pinfunction "19(RX1)_19") (pintype "bidirectional"))
    )
    (net (code "320") (name "unconnected-(U2-20(SDA)-Pad20)") (class "Default")
      (node (ref "U2") (pin "20") (pinfunction "20(SDA)_20") (pintype "bidirectional"))
    )
    (net (code "321") (name "unconnected-(U2-21(SCL)-Pad21)") (class "Default")
      (node (ref "U2") (pin "21") (pinfunction "21(SCL)_21") (pintype "bidirectional"))
    )
    (net (code "322") (name "unconnected-(U2-Pad2)") (class "Default")
      (node (ref "U2") (pin "2") (pinfunction "2_2") (pintype "bidirectional"))
    )
    (net (code "323") (name "unconnected-(U2-Pad3)") (class "Default")
      (node (ref "U2") (pin "3") (pinfunction "3_3") (pintype "bidirectional"))
    )
    (net (code "324") (name "unconnected-(U2-Pad3.3V)") (class "Default")
      (node (ref "U2") (pin "3.3V") (pinfunction "3.3V_3.3V") (pintype "bidirectional"))
    )
    (net (code "325") (name "unconnected-(U2-Pad4)") (class "Default")
      (node (ref "U2") (pin "4") (pinfunction "4_4") (pintype "bidirectional"))
    )
    (net (code "326") (name "unconnected-(U2-Pad5)") (class "Default")
      (node (ref "U2") (pin "5") (pinfunction "5_5") (pintype "bidirectional"))
    )
    (net (code "327") (name "unconnected-(U2-Pad38)") (class "Default")
      (node (ref "U2") (pin "38") (pinfunction "38_38") (pintype "bidirectional"))
    )
    (net (code "328") (name "unconnected-(U2-Pad39)") (class "Default")
      (node (ref "U2") (pin "39") (pinfunction "39_39") (pintype "bidirectional"))
    )
    (net (code "329") (name "unconnected-(U2-Pad40)") (class "Default")
      (node (ref "U2") (pin "40") (pinfunction "40_40") (pintype "bidirectional"))
    )
    (net (code "330") (name "unconnected-(U2-Pad41)") (class "Default")
      (node (ref "U2") (pin "41") (pinfunction "41_41") (pintype "bidirectional"))
    )
    (net (code "331") (name "unconnected-(U2-Pad42)") (class "Default")
      (node (ref "U2") (pin "42") (pinfunction "42_42") (pintype "bidirectional"))
    )
    (net (code "332") (name "unconnected-(U2-Pad43)") (class "Default")
      (node (ref "U2") (pin "43") (pinfunction "43_43") (pintype "bidirectional"))
    )
    (net (code "333") (name "unconnected-(U2-Pad44)") (class "Default")
      (node (ref "U2") (pin "44") (pinfunction "44_44") (pintype "bidirectional"))
    )
    (net (code "334") (name "unconnected-(U2-Pad45)") (class "Default")
      (node (ref "U2") (pin "45") (pinfunction "45_45") (pintype "bidirectional"))
    )
    (net (code "335") (name "unconnected-(U2-Pad46)") (class "Default")
      (node (ref "U2") (pin "46") (pinfunction "46_46") (pintype "bidirectional"))
    )
    (net (code "336") (name "unconnected-(U2-Pad47)") (class "Default")
      (node (ref "U2") (pin "47") (pinfunction "47_47") (pintype "bidirectional"))
    )
    (net (code "337") (name "unconnected-(U2-Pad48)") (class "Default")
      (node (ref "U2") (pin "48") (pinfunction "48_48") (pintype "bidirectional"))
    )
    (net (code "338") (name "unconnected-(U2-Pad49)") (class "Default")
      (node (ref "U2") (pin "49") (pinfunction "49_49") (pintype "bidirectional"))
    )
    (net (code "339") (name "unconnected-(U2-Pad50)") (class "Default")
      (node (ref "U2") (pin "50") (pinfunction "50_50") (pintype "bidirectional"))
    )
    (net (code "340") (name "unconnected-(U2-Pad51)") (class "Default")
      (node (ref "U2") (pin "51") (pinfunction "51_51") (pintype "bidirectional"))
    )
    (net (code "341") (name "unconnected-(U2-Pad52)") (class "Default")
      (node (ref "U2") (pin "52") (pinfunction "52_52") (pintype "bidirectional"))
    )
    (net (code "342") (name "unconnected-(U2-Pad53)") (class "Default")
      (node (ref "U2") (pin "53") (pinfunction "53_53") (pintype "bidirectional"))
    )
    (net (code "343") (name "unconnected-(U2-PadA3)") (class "Default")
      (node (ref "U2") (pin "A3") (pinfunction "A3_A3") (pintype "bidirectional"))
    )
    (net (code "344") (name "unconnected-(U2-PadA4)") (class "Default")
      (node (ref "U2") (pin "A4") (pinfunction "A4_A4") (pintype "bidirectional"))
    )
    (net (code "345") (name "unconnected-(U2-PadA5)") (class "Default")
      (node (ref "U2") (pin "A5") (pinfunction "A5_A5") (pintype "bidirectional"))
    )
    (net (code "346") (name "unconnected-(U2-PadA6)") (class "Default")
      (node (ref "U2") (pin "A6") (pinfunction "A6_A6") (pintype "bidirectional"))
    )
    (net (code "347") (name "unconnected-(U2-PadA7)") (class "Default")
      (node (ref "U2") (pin "A7") (pinfunction "A7_A7") (pintype "bidirectional"))
    )
    (net (code "348") (name "unconnected-(U2-PadA8)") (class "Default")
      (node (ref "U2") (pin "A8") (pinfunction "A8_A8") (pintype "bidirectional"))
    )
    (net (code "349") (name "unconnected-(U2-PadA9)") (class "Default")
      (node (ref "U2") (pin "A9") (pinfunction "A9_A9") (pintype "bidirectional"))
    )
    (net (code "350") (name "unconnected-(U2-PadA10)") (class "Default")
      (node (ref "U2") (pin "A10") (pinfunction "A10_A10") (pintype "bidirectional"))
    )
    (net (code "351") (name "unconnected-(U2-PadA11)") (class "Default")
      (node (ref "U2") (pin "A11") (pinfunction "A11_A11") (pintype "bidirectional"))
    )
    (net (code "352") (name "unconnected-(U2-PadA12)") (class "Default")
      (node (ref "U2") (pin "A12") (pinfunction "A12_A12") (pintype "bidirectional"))
    )
    (net (code "353") (name "unconnected-(U2-PadA13)") (class "Default")
      (node (ref "U2") (pin "A13") (pinfunction "A13_A13") (pintype "bidirectional"))
    )
    (net (code "354") (name "unconnected-(U2-PadA14)") (class "Default")
      (node (ref "U2") (pin "A14") (pinfunction "A14_A14") (pintype "bidirectional"))
    )
    (net (code "355") (name "unconnected-(U2-PadA15)") (class "Default")
      (node (ref "U2") (pin "A15") (pinfunction "A15_A15") (pintype "bidirectional"))
    )
    (net (code "356") (name "unconnected-(U2-PadAREF)") (class "Default")
      (node (ref "U2") (pin "AREF") (pinfunction "AREF_AREF") (pintype "bidirectional"))
    )
    (net (code "357") (name "unconnected-(U2-PadRESET)") (class "Default")
      (node (ref "U2") (pin "RESET") (pinfunction "RESET_RESET") (pintype "bidirectional"))
    )
  )
)
